# remote_v0_14_fa8ef31d.net
KiCad netlist of a schematic drawn in EAGLE
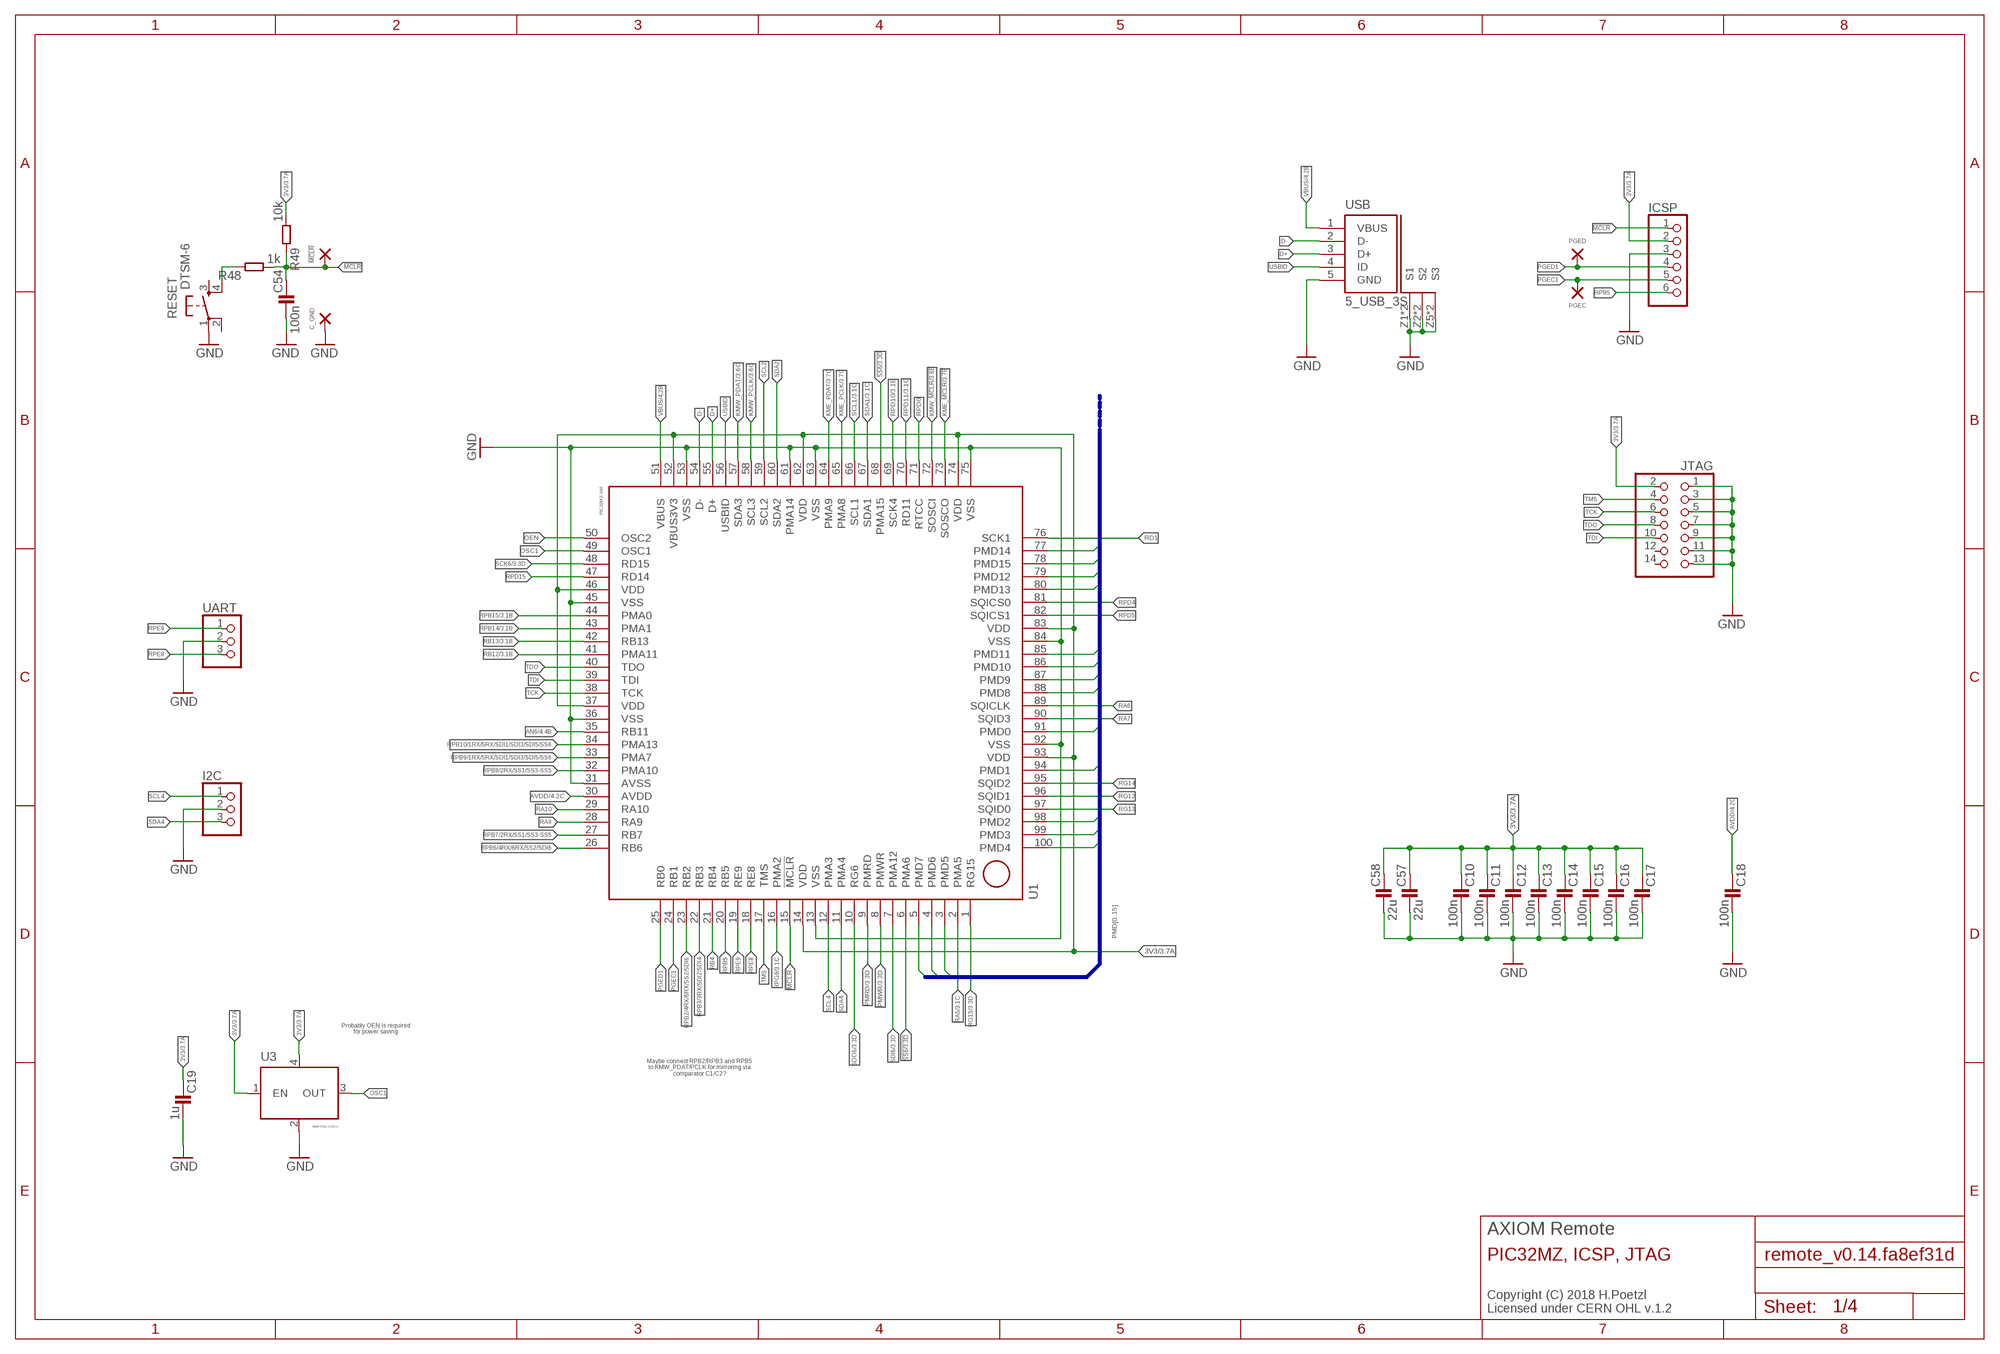
[diagram p0: schematic, sheet 1]
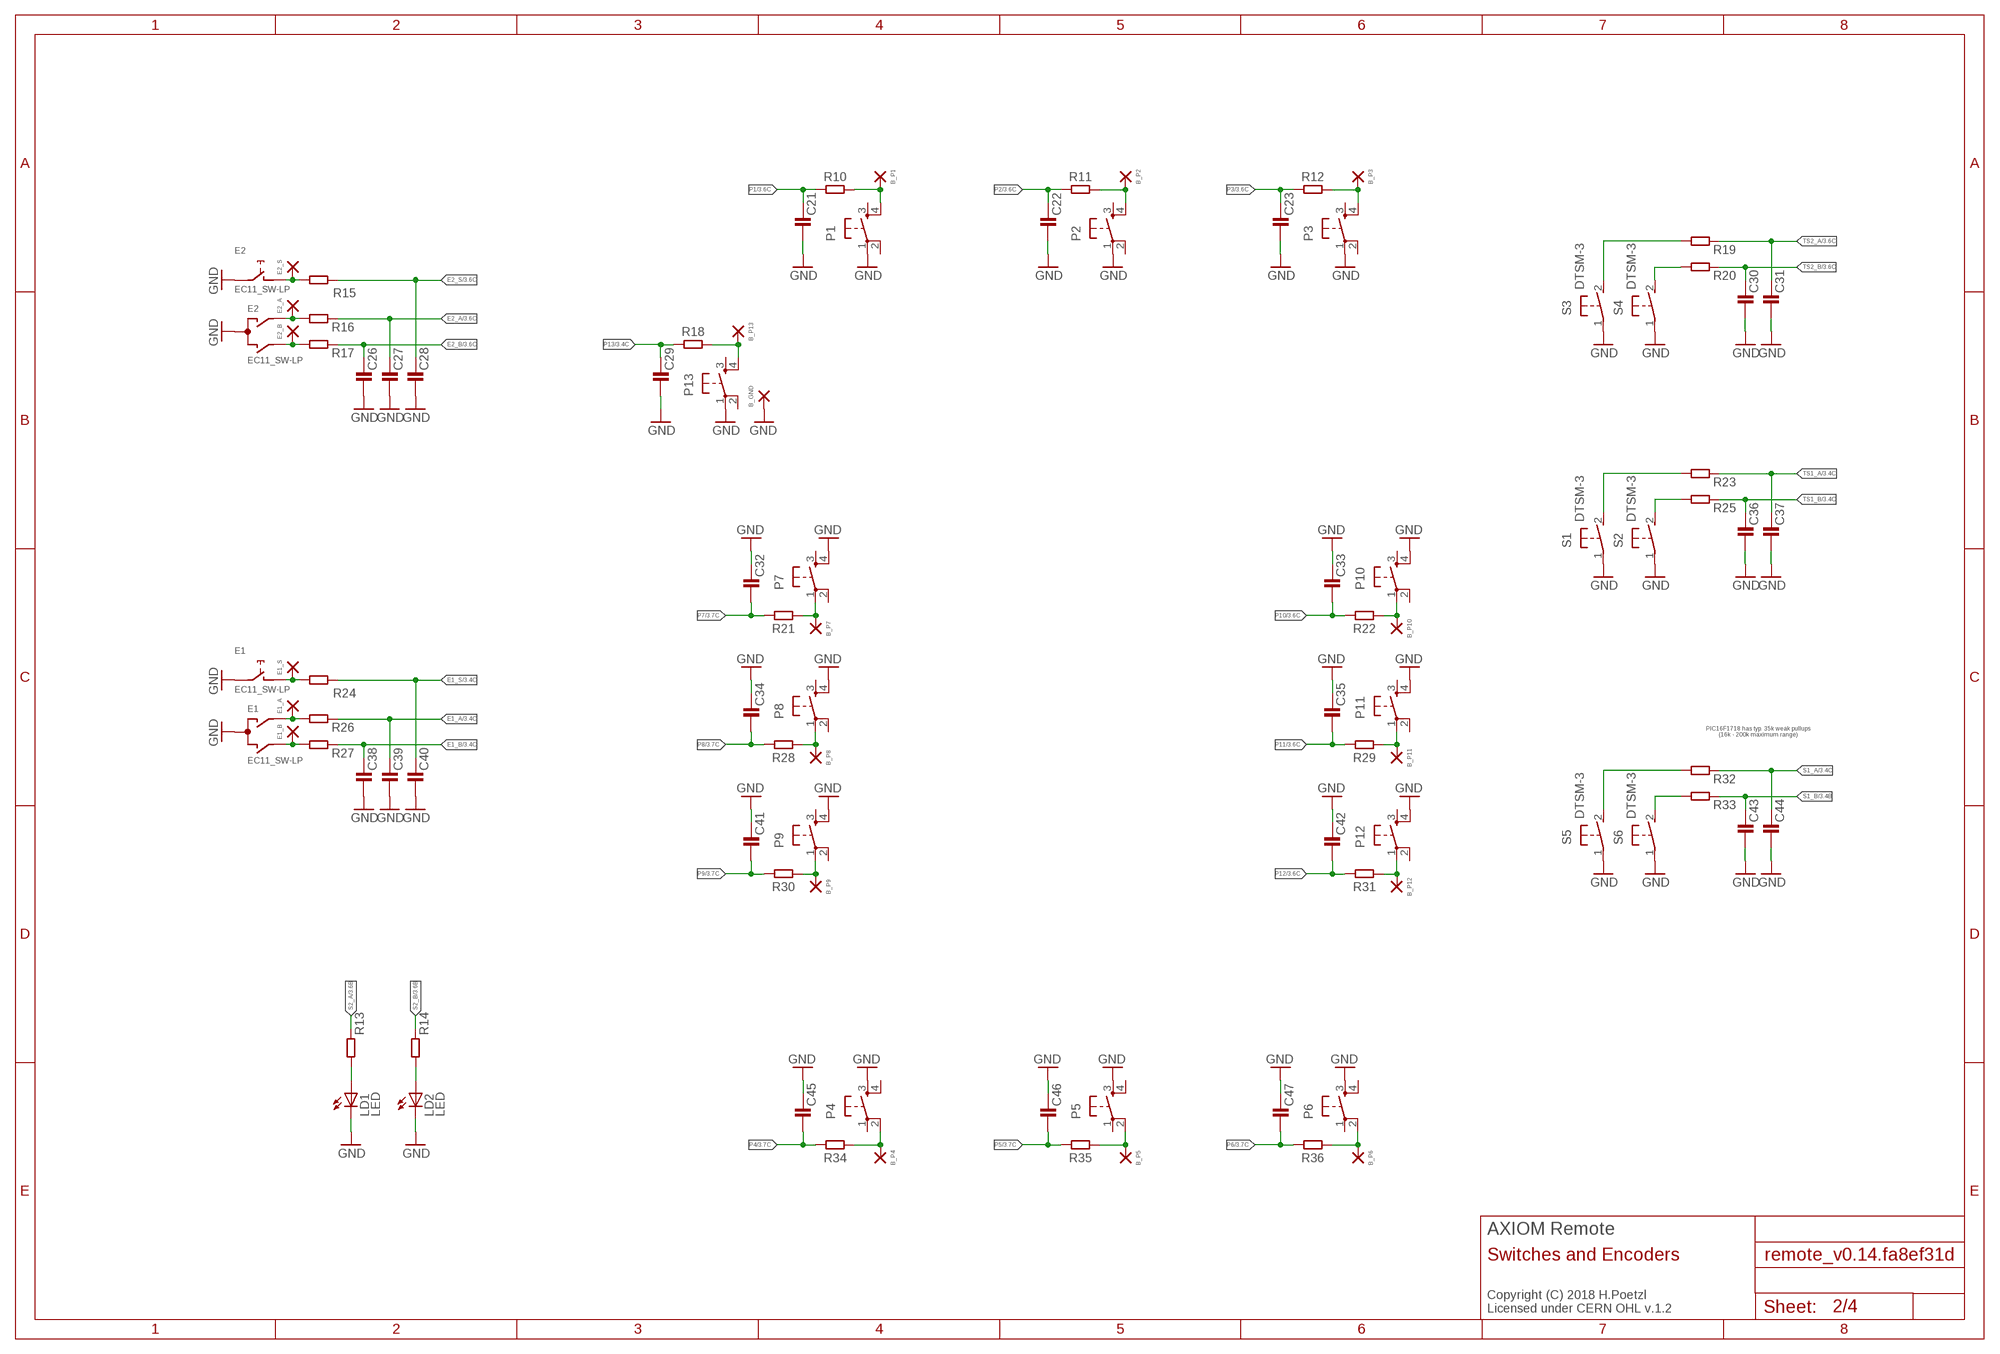
[diagram p1: schematic, sheet 2]
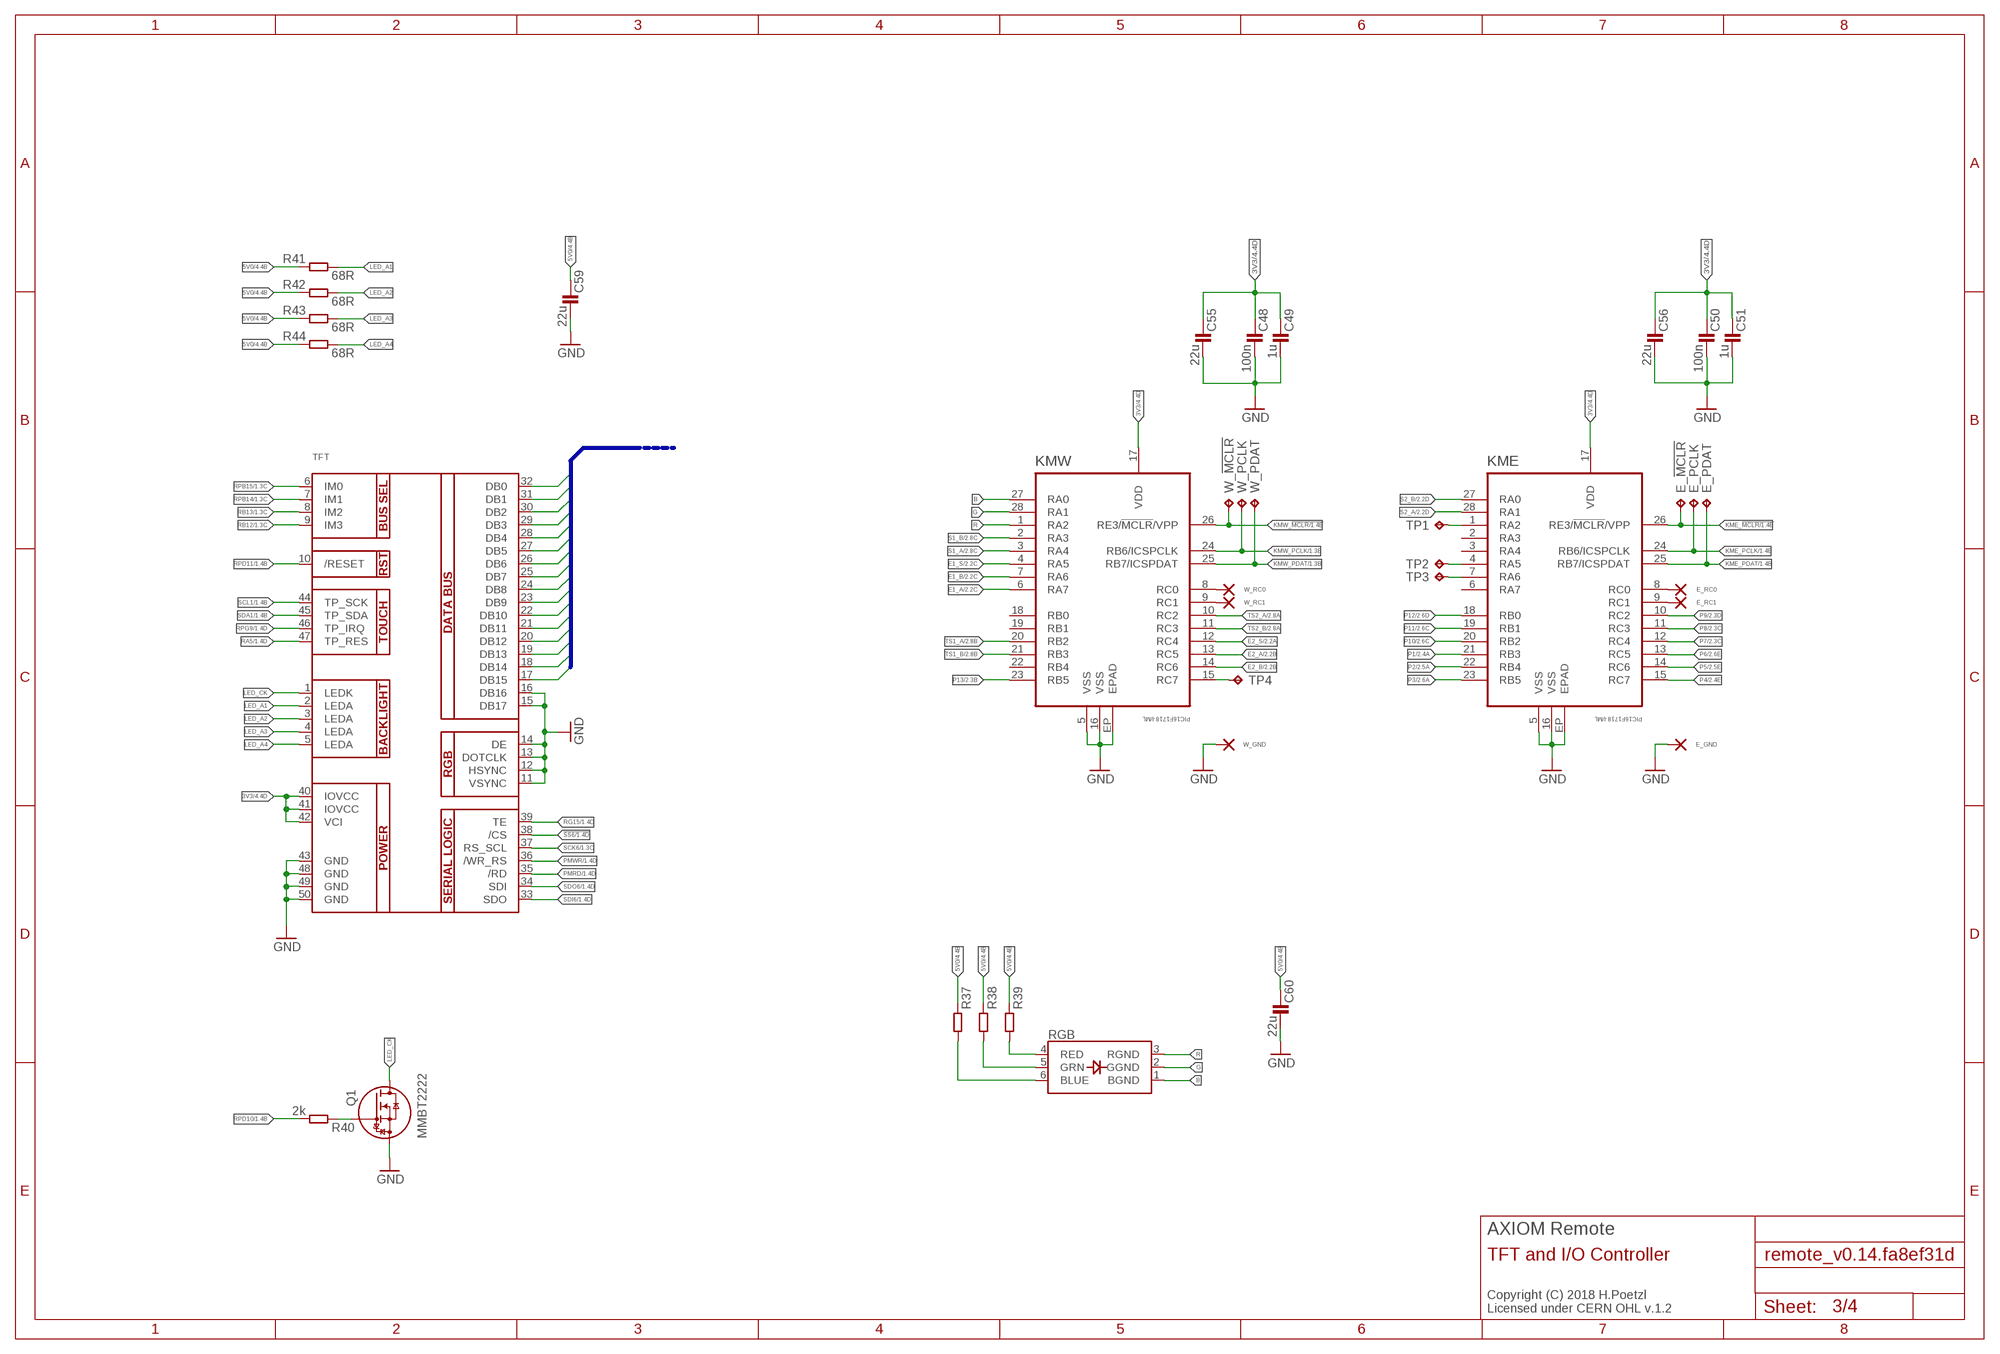
[diagram p2: schematic, sheet 3]
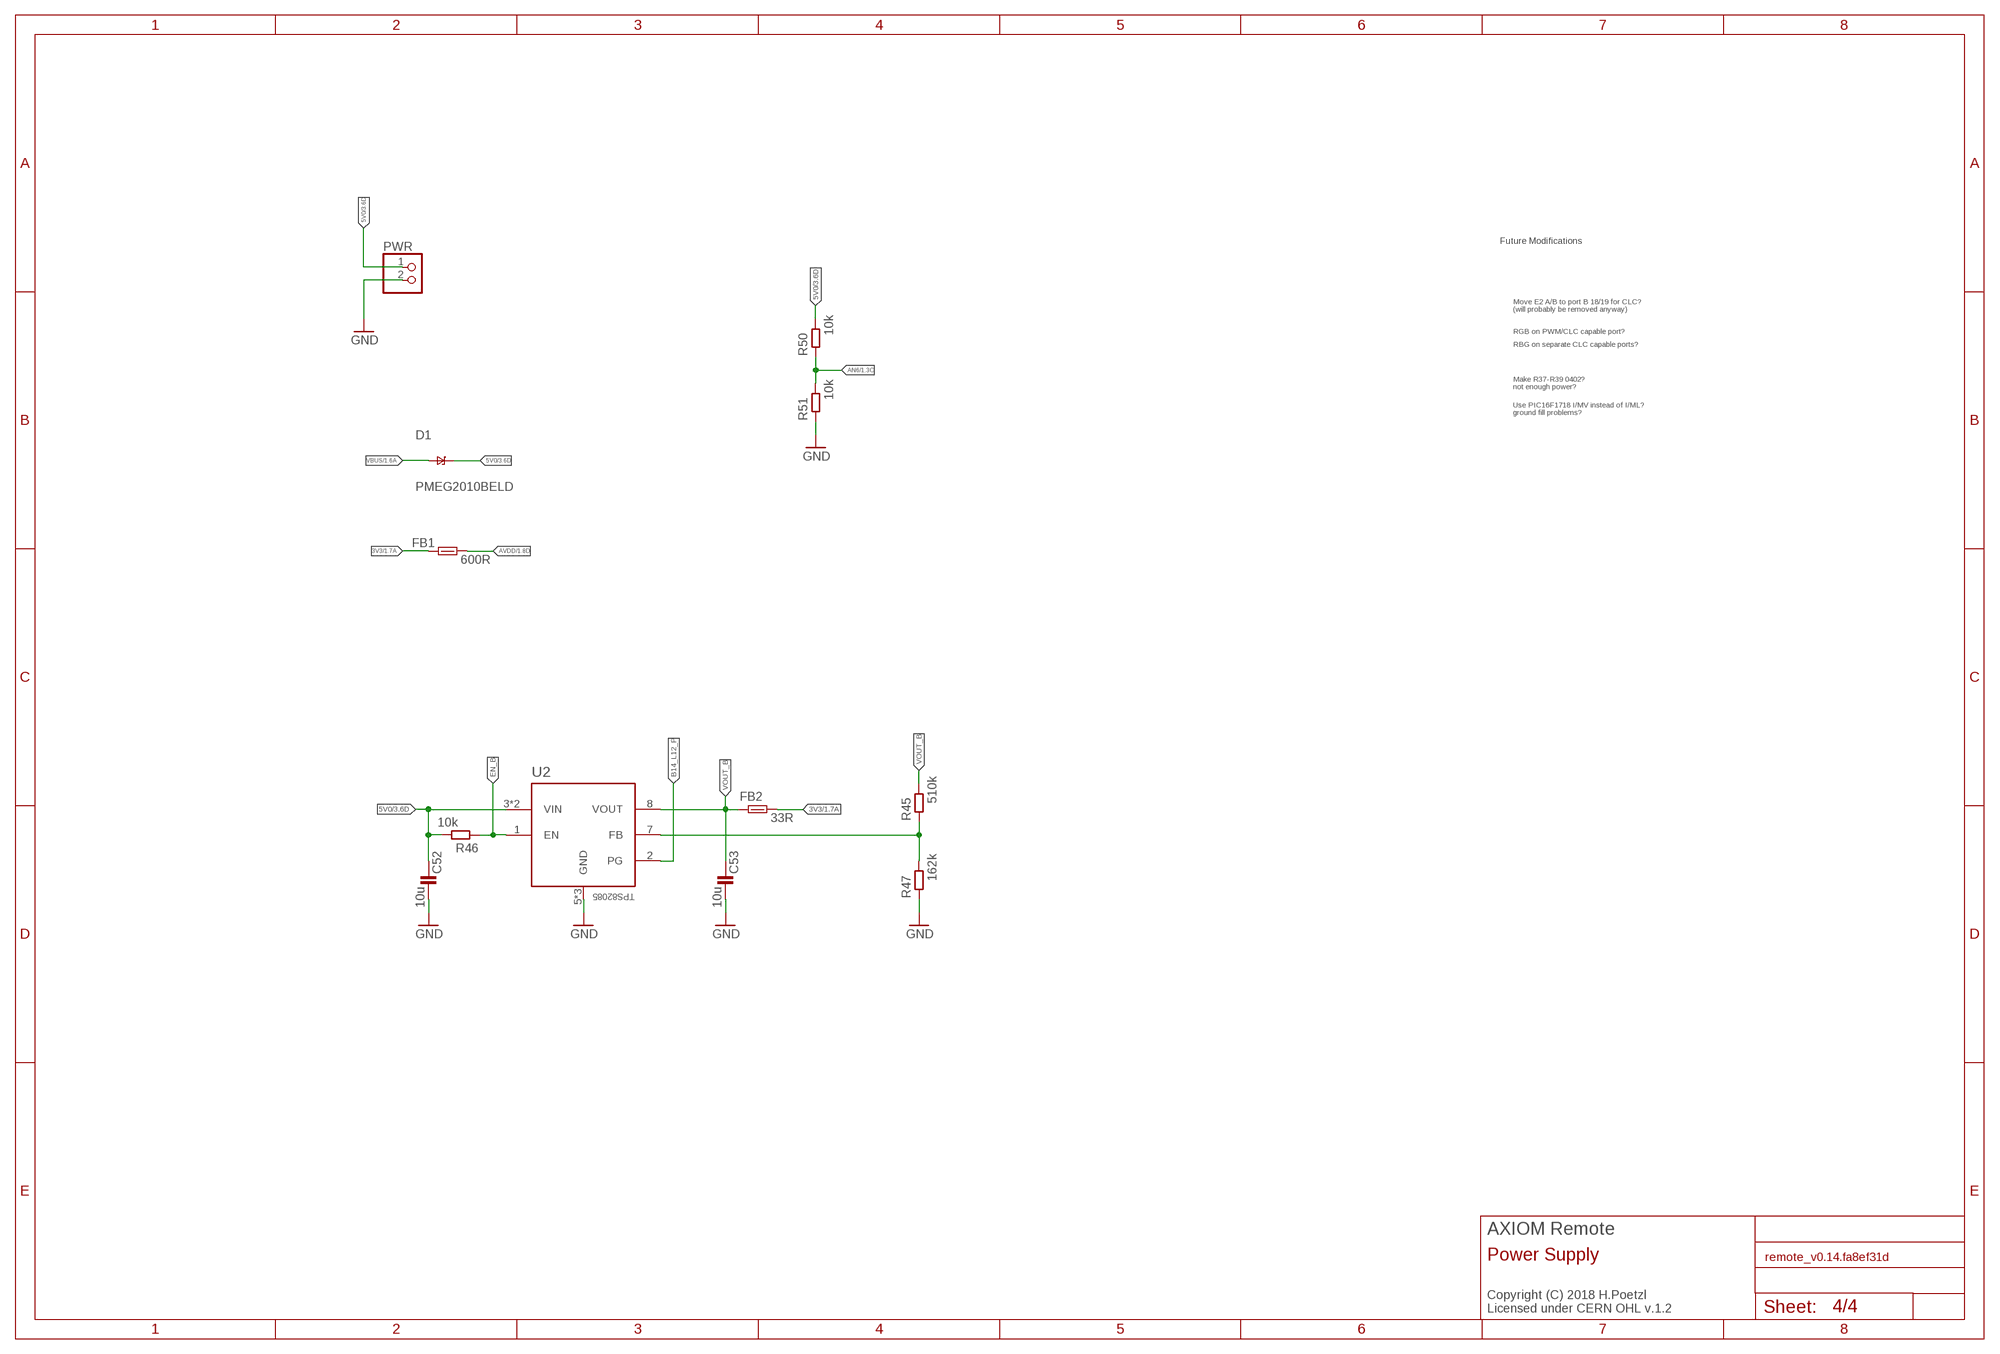
[diagram p3: schematic, sheet 4]

(export (version "E")
  (design (tool "Eeschema 10.0.6"))
  (components
    (comp (ref "B_GND")
      (value "SMD-PAD50X100")
      (footprint "eagle-import:50X100-MIL")
      (libsource (lib "eagle-import") (part "SMD-PAD50X100"))
    )
    (comp (ref "B_P1")
      (value "SMD-PAD50X100")
      (footprint "eagle-import:50X100-MIL")
      (libsource (lib "eagle-import") (part "SMD-PAD50X100"))
    )
    (comp (ref "B_P2")
      (value "SMD-PAD50X100")
      (footprint "eagle-import:50X100-MIL")
      (libsource (lib "eagle-import") (part "SMD-PAD50X100"))
    )
    (comp (ref "B_P3")
      (value "SMD-PAD50X100")
      (footprint "eagle-import:50X100-MIL")
      (libsource (lib "eagle-import") (part "SMD-PAD50X100"))
    )
    (comp (ref "B_P4")
      (value "SMD-PAD50X100")
      (footprint "eagle-import:50X100-MIL")
      (libsource (lib "eagle-import") (part "SMD-PAD50X100"))
    )
    (comp (ref "B_P5")
      (value "SMD-PAD50X100")
      (footprint "eagle-import:50X100-MIL")
      (libsource (lib "eagle-import") (part "SMD-PAD50X100"))
    )
    (comp (ref "B_P6")
      (value "SMD-PAD50X100")
      (footprint "eagle-import:50X100-MIL")
      (libsource (lib "eagle-import") (part "SMD-PAD50X100"))
    )
    (comp (ref "B_P7")
      (value "SMD-PAD50X100")
      (footprint "eagle-import:50X100-MIL")
      (libsource (lib "eagle-import") (part "SMD-PAD50X100"))
    )
    (comp (ref "B_P8")
      (value "SMD-PAD50X100")
      (footprint "eagle-import:50X100-MIL")
      (libsource (lib "eagle-import") (part "SMD-PAD50X100"))
    )
    (comp (ref "B_P9")
      (value "SMD-PAD50X100")
      (footprint "eagle-import:50X100-MIL")
      (libsource (lib "eagle-import") (part "SMD-PAD50X100"))
    )
    (comp (ref "B_P10")
      (value "SMD-PAD50X100")
      (footprint "eagle-import:50X100-MIL")
      (libsource (lib "eagle-import") (part "SMD-PAD50X100"))
    )
    (comp (ref "B_P11")
      (value "SMD-PAD50X100")
      (footprint "eagle-import:50X100-MIL")
      (libsource (lib "eagle-import") (part "SMD-PAD50X100"))
    )
    (comp (ref "B_P12")
      (value "SMD-PAD50X100")
      (footprint "eagle-import:50X100-MIL")
      (libsource (lib "eagle-import") (part "SMD-PAD50X100"))
    )
    (comp (ref "B_P13")
      (value "SMD-PAD50X100")
      (footprint "eagle-import:50X100-MIL")
      (libsource (lib "eagle-import") (part "SMD-PAD50X100"))
    )
    (comp (ref "C21")
      (value "C0402-C")
      (footprint "eagle-import:0402-C")
      (libsource (lib "eagle-import") (part "C0402-C"))
    )
    (comp (ref "C22")
      (value "C0402-C")
      (footprint "eagle-import:0402-C")
      (libsource (lib "eagle-import") (part "C0402-C"))
    )
    (comp (ref "C23")
      (value "C0402-C")
      (footprint "eagle-import:0402-C")
      (libsource (lib "eagle-import") (part "C0402-C"))
    )
    (comp (ref "C26")
      (value "C0402-C")
      (footprint "eagle-import:0402-C")
      (libsource (lib "eagle-import") (part "C0402-C"))
    )
    (comp (ref "C27")
      (value "C0402-C")
      (footprint "eagle-import:0402-C")
      (libsource (lib "eagle-import") (part "C0402-C"))
    )
    (comp (ref "C28")
      (value "C0402-C")
      (footprint "eagle-import:0402-C")
      (libsource (lib "eagle-import") (part "C0402-C"))
    )
    (comp (ref "C29")
      (value "C0402-C")
      (footprint "eagle-import:0402-C")
      (libsource (lib "eagle-import") (part "C0402-C"))
    )
    (comp (ref "C30")
      (value "C0402-C")
      (footprint "eagle-import:0402-C")
      (libsource (lib "eagle-import") (part "C0402-C"))
    )
    (comp (ref "C31")
      (value "C0402-C")
      (footprint "eagle-import:0402-C")
      (libsource (lib "eagle-import") (part "C0402-C"))
    )
    (comp (ref "C32")
      (value "C0402-C")
      (footprint "eagle-import:0402-C")
      (libsource (lib "eagle-import") (part "C0402-C"))
    )
    (comp (ref "C33")
      (value "C0402-C")
      (footprint "eagle-import:0402-C")
      (libsource (lib "eagle-import") (part "C0402-C"))
    )
    (comp (ref "C34")
      (value "C0402-C")
      (footprint "eagle-import:0402-C")
      (libsource (lib "eagle-import") (part "C0402-C"))
    )
    (comp (ref "C35")
      (value "C0402-C")
      (footprint "eagle-import:0402-C")
      (libsource (lib "eagle-import") (part "C0402-C"))
    )
    (comp (ref "C36")
      (value "C0402-C")
      (footprint "eagle-import:0402-C")
      (libsource (lib "eagle-import") (part "C0402-C"))
    )
    (comp (ref "C37")
      (value "C0402-C")
      (footprint "eagle-import:0402-C")
      (libsource (lib "eagle-import") (part "C0402-C"))
    )
    (comp (ref "C38")
      (value "C0402-C")
      (footprint "eagle-import:0402-C")
      (libsource (lib "eagle-import") (part "C0402-C"))
    )
    (comp (ref "C39")
      (value "C0402-C")
      (footprint "eagle-import:0402-C")
      (libsource (lib "eagle-import") (part "C0402-C"))
    )
    (comp (ref "C40")
      (value "C0402-C")
      (footprint "eagle-import:0402-C")
      (libsource (lib "eagle-import") (part "C0402-C"))
    )
    (comp (ref "C41")
      (value "C0402-C")
      (footprint "eagle-import:0402-C")
      (libsource (lib "eagle-import") (part "C0402-C"))
    )
    (comp (ref "C42")
      (value "C0402-C")
      (footprint "eagle-import:0402-C")
      (libsource (lib "eagle-import") (part "C0402-C"))
    )
    (comp (ref "C43")
      (value "C0402-C")
      (footprint "eagle-import:0402-C")
      (libsource (lib "eagle-import") (part "C0402-C"))
    )
    (comp (ref "C44")
      (value "C0402-C")
      (footprint "eagle-import:0402-C")
      (libsource (lib "eagle-import") (part "C0402-C"))
    )
    (comp (ref "C45")
      (value "C0402-C")
      (footprint "eagle-import:0402-C")
      (libsource (lib "eagle-import") (part "C0402-C"))
    )
    (comp (ref "C46")
      (value "C0402-C")
      (footprint "eagle-import:0402-C")
      (libsource (lib "eagle-import") (part "C0402-C"))
    )
    (comp (ref "C47")
      (value "C0402-C")
      (footprint "eagle-import:0402-C")
      (libsource (lib "eagle-import") (part "C0402-C"))
    )
    (comp (ref "E1")
      (value "EC11_SW-LP")
      (footprint "eagle-import:EC11_SW-LP")
      (libsource (lib "eagle-import") (part "EC11_SW-LP"))
    )
    (comp (ref "E1_A")
      (value "SMD-PAD50X100")
      (footprint "eagle-import:50X100-MIL")
      (libsource (lib "eagle-import") (part "SMD-PAD50X100"))
    )
    (comp (ref "E1_B")
      (value "SMD-PAD50X100")
      (footprint "eagle-import:50X100-MIL")
      (libsource (lib "eagle-import") (part "SMD-PAD50X100"))
    )
    (comp (ref "E1_S")
      (value "SMD-PAD50X100")
      (footprint "eagle-import:50X100-MIL")
      (libsource (lib "eagle-import") (part "SMD-PAD50X100"))
    )
    (comp (ref "E2")
      (value "EC11_SW-LP")
      (footprint "eagle-import:EC11_SW-LP")
      (libsource (lib "eagle-import") (part "EC11_SW-LP"))
    )
    (comp (ref "E2_A")
      (value "SMD-PAD50X100")
      (footprint "eagle-import:50X100-MIL")
      (libsource (lib "eagle-import") (part "SMD-PAD50X100"))
    )
    (comp (ref "E2_B")
      (value "SMD-PAD50X100")
      (footprint "eagle-import:50X100-MIL")
      (libsource (lib "eagle-import") (part "SMD-PAD50X100"))
    )
    (comp (ref "E2_S")
      (value "SMD-PAD50X100")
      (footprint "eagle-import:50X100-MIL")
      (libsource (lib "eagle-import") (part "SMD-PAD50X100"))
    )
    (comp (ref "LD1")
      (value "LED")
      (footprint "eagle-import:CHIPLED_0603")
      (libsource (lib "eagle-import") (part "LED"))
    )
    (comp (ref "LD2")
      (value "LED")
      (footprint "eagle-import:CHIPLED_0603")
      (libsource (lib "eagle-import") (part "LED"))
    )
    (comp (ref "P1")
      (value "DTSM-6THT")
      (footprint "eagle-import:6X6-THT")
      (libsource (lib "eagle-import") (part "DTSM-6THT"))
    )
    (comp (ref "P2")
      (value "DTSM-6THT")
      (footprint "eagle-import:6X6-THT")
      (libsource (lib "eagle-import") (part "DTSM-6THT"))
    )
    (comp (ref "P3")
      (value "DTSM-6THT")
      (footprint "eagle-import:6X6-THT")
      (libsource (lib "eagle-import") (part "DTSM-6THT"))
    )
    (comp (ref "P4")
      (value "DTSM-6THT")
      (footprint "eagle-import:6X6-THT")
      (libsource (lib "eagle-import") (part "DTSM-6THT"))
    )
    (comp (ref "P5")
      (value "DTSM-6THT")
      (footprint "eagle-import:6X6-THT")
      (libsource (lib "eagle-import") (part "DTSM-6THT"))
    )
    (comp (ref "P6")
      (value "DTSM-6THT")
      (footprint "eagle-import:6X6-THT")
      (libsource (lib "eagle-import") (part "DTSM-6THT"))
    )
    (comp (ref "P7")
      (value "DTSM-6THT")
      (footprint "eagle-import:6X6-THT")
      (libsource (lib "eagle-import") (part "DTSM-6THT"))
    )
    (comp (ref "P8")
      (value "DTSM-6THT")
      (footprint "eagle-import:6X6-THT")
      (libsource (lib "eagle-import") (part "DTSM-6THT"))
    )
    (comp (ref "P9")
      (value "DTSM-6THT")
      (footprint "eagle-import:6X6-THT")
      (libsource (lib "eagle-import") (part "DTSM-6THT"))
    )
    (comp (ref "P10")
      (value "DTSM-6THT")
      (footprint "eagle-import:6X6-THT")
      (libsource (lib "eagle-import") (part "DTSM-6THT"))
    )
    (comp (ref "P11")
      (value "DTSM-6THT")
      (footprint "eagle-import:6X6-THT")
      (libsource (lib "eagle-import") (part "DTSM-6THT"))
    )
    (comp (ref "P12")
      (value "DTSM-6THT")
      (footprint "eagle-import:6X6-THT")
      (libsource (lib "eagle-import") (part "DTSM-6THT"))
    )
    (comp (ref "P13")
      (value "DTSM-6THT")
      (footprint "eagle-import:6X6-THT")
      (libsource (lib "eagle-import") (part "DTSM-6THT"))
    )
    (comp (ref "R10")
      (value "R0402-C")
      (footprint "eagle-import:0402-C")
      (libsource (lib "eagle-import") (part "R0402-C"))
    )
    (comp (ref "R11")
      (value "R0402-C")
      (footprint "eagle-import:0402-C")
      (libsource (lib "eagle-import") (part "R0402-C"))
    )
    (comp (ref "R12")
      (value "R0402-C")
      (footprint "eagle-import:0402-C")
      (libsource (lib "eagle-import") (part "R0402-C"))
    )
    (comp (ref "R13")
      (value "R0402-C")
      (footprint "eagle-import:0402-C")
      (libsource (lib "eagle-import") (part "R0402-C"))
    )
    (comp (ref "R14")
      (value "R0402-C")
      (footprint "eagle-import:0402-C")
      (libsource (lib "eagle-import") (part "R0402-C"))
    )
    (comp (ref "R15")
      (value "R0402-C")
      (footprint "eagle-import:0402-C")
      (libsource (lib "eagle-import") (part "R0402-C"))
    )
    (comp (ref "R16")
      (value "R0402-C")
      (footprint "eagle-import:0402-C")
      (libsource (lib "eagle-import") (part "R0402-C"))
    )
    (comp (ref "R17")
      (value "R0402-C")
      (footprint "eagle-import:0402-C")
      (libsource (lib "eagle-import") (part "R0402-C"))
    )
    (comp (ref "R18")
      (value "R0402-C")
      (footprint "eagle-import:0402-C")
      (libsource (lib "eagle-import") (part "R0402-C"))
    )
    (comp (ref "R19")
      (value "R0402-C")
      (footprint "eagle-import:0402-C")
      (libsource (lib "eagle-import") (part "R0402-C"))
    )
    (comp (ref "R20")
      (value "R0402-C")
      (footprint "eagle-import:0402-C")
      (libsource (lib "eagle-import") (part "R0402-C"))
    )
    (comp (ref "R21")
      (value "R0402-C")
      (footprint "eagle-import:0402-C")
      (libsource (lib "eagle-import") (part "R0402-C"))
    )
    (comp (ref "R22")
      (value "R0402-C")
      (footprint "eagle-import:0402-C")
      (libsource (lib "eagle-import") (part "R0402-C"))
    )
    (comp (ref "R23")
      (value "R0402-C")
      (footprint "eagle-import:0402-C")
      (libsource (lib "eagle-import") (part "R0402-C"))
    )
    (comp (ref "R24")
      (value "R0402-C")
      (footprint "eagle-import:0402-C")
      (libsource (lib "eagle-import") (part "R0402-C"))
    )
    (comp (ref "R25")
      (value "R0402-C")
      (footprint "eagle-import:0402-C")
      (libsource (lib "eagle-import") (part "R0402-C"))
    )
    (comp (ref "R26")
      (value "R0402-C")
      (footprint "eagle-import:0402-C")
      (libsource (lib "eagle-import") (part "R0402-C"))
    )
    (comp (ref "R27")
      (value "R0402-C")
      (footprint "eagle-import:0402-C")
      (libsource (lib "eagle-import") (part "R0402-C"))
    )
    (comp (ref "R28")
      (value "R0402-C")
      (footprint "eagle-import:0402-C")
      (libsource (lib "eagle-import") (part "R0402-C"))
    )
    (comp (ref "R29")
      (value "R0402-C")
      (footprint "eagle-import:0402-C")
      (libsource (lib "eagle-import") (part "R0402-C"))
    )
    (comp (ref "R30")
      (value "R0402-C")
      (footprint "eagle-import:0402-C")
      (libsource (lib "eagle-import") (part "R0402-C"))
    )
    (comp (ref "R31")
      (value "R0402-C")
      (footprint "eagle-import:0402-C")
      (libsource (lib "eagle-import") (part "R0402-C"))
    )
    (comp (ref "R32")
      (value "R0402-C")
      (footprint "eagle-import:0402-C")
      (libsource (lib "eagle-import") (part "R0402-C"))
    )
    (comp (ref "R33")
      (value "R0402-C")
      (footprint "eagle-import:0402-C")
      (libsource (lib "eagle-import") (part "R0402-C"))
    )
    (comp (ref "R34")
      (value "R0402-C")
      (footprint "eagle-import:0402-C")
      (libsource (lib "eagle-import") (part "R0402-C"))
    )
    (comp (ref "R35")
      (value "R0402-C")
      (footprint "eagle-import:0402-C")
      (libsource (lib "eagle-import") (part "R0402-C"))
    )
    (comp (ref "R36")
      (value "R0402-C")
      (footprint "eagle-import:0402-C")
      (libsource (lib "eagle-import") (part "R0402-C"))
    )
    (comp (ref "S1")
      (value "DTSM-3")
      (footprint "eagle-import:DTSM-3")
      (libsource (lib "eagle-import") (part "DTSM-3"))
    )
    (comp (ref "S2")
      (value "DTSM-3")
      (footprint "eagle-import:DTSM-3")
      (libsource (lib "eagle-import") (part "DTSM-3"))
    )
    (comp (ref "S3")
      (value "DTSM-3")
      (footprint "eagle-import:DTSM-3")
      (libsource (lib "eagle-import") (part "DTSM-3"))
    )
    (comp (ref "S4")
      (value "DTSM-3")
      (footprint "eagle-import:DTSM-3")
      (libsource (lib "eagle-import") (part "DTSM-3"))
    )
    (comp (ref "S5")
      (value "DTSM-3")
      (footprint "eagle-import:DTSM-3")
      (libsource (lib "eagle-import") (part "DTSM-3"))
    )
    (comp (ref "S6")
      (value "DTSM-3")
      (footprint "eagle-import:DTSM-3")
      (libsource (lib "eagle-import") (part "DTSM-3"))
    )
    (comp (ref "!MCLR")
      (value "SMD-PAD50X100")
      (footprint "eagle-import:50X100-MIL")
      (libsource (lib "eagle-import") (part "SMD-PAD50X100"))
    )
    (comp (ref "C10")
      (value "100n")
      (footprint "eagle-import:0402-C")
      (libsource (lib "eagle-import") (part "C0402-C"))
    )
    (comp (ref "C11")
      (value "100n")
      (footprint "eagle-import:0402-C")
      (libsource (lib "eagle-import") (part "C0402-C"))
    )
    (comp (ref "C12")
      (value "100n")
      (footprint "eagle-import:0402-C")
      (libsource (lib "eagle-import") (part "C0402-C"))
    )
    (comp (ref "C13")
      (value "100n")
      (footprint "eagle-import:0402-C")
      (libsource (lib "eagle-import") (part "C0402-C"))
    )
    (comp (ref "C14")
      (value "100n")
      (footprint "eagle-import:0402-C")
      (libsource (lib "eagle-import") (part "C0402-C"))
    )
    (comp (ref "C15")
      (value "100n")
      (footprint "eagle-import:0402-C")
      (libsource (lib "eagle-import") (part "C0402-C"))
    )
    (comp (ref "C16")
      (value "100n")
      (footprint "eagle-import:0402-C")
      (libsource (lib "eagle-import") (part "C0402-C"))
    )
    (comp (ref "C17")
      (value "100n")
      (footprint "eagle-import:0402-C")
      (libsource (lib "eagle-import") (part "C0402-C"))
    )
    (comp (ref "C18")
      (value "100n")
      (footprint "eagle-import:0402-C")
      (libsource (lib "eagle-import") (part "C0402-C"))
    )
    (comp (ref "C19")
      (value "1u")
      (footprint "eagle-import:0402-C")
      (libsource (lib "eagle-import") (part "C0402-C"))
    )
    (comp (ref "C54")
      (value "100n")
      (footprint "eagle-import:0402-C")
      (libsource (lib "eagle-import") (part "C0402-C"))
    )
    (comp (ref "C57")
      (value "22u")
      (footprint "eagle-import:0805-C")
      (libsource (lib "eagle-import") (part "C0805-C"))
    )
    (comp (ref "C58")
      (value "22u")
      (footprint "eagle-import:0805-C")
      (libsource (lib "eagle-import") (part "C0805-C"))
    )
    (comp (ref "C_GND")
      (value "SMD-PAD50X100")
      (footprint "eagle-import:50X100-MIL")
      (libsource (lib "eagle-import") (part "SMD-PAD50X100"))
    )
    (comp (ref "I2C")
      (value "PINHD-1X03_2.54-90°")
      (footprint "eagle-import:1X03_90")
      (libsource (lib "eagle-import") (part "PINHD-1X03_2.54-90°"))
    )
    (comp (ref "ICSP")
      (value "PINHD-1X6/90")
      (footprint "eagle-import:1X06_90")
      (libsource (lib "eagle-import") (part "PINHD-1X6/90"))
    )
    (comp (ref "JTAG")
      (value "PINHD-2X07_2.00")
      (footprint "eagle-import:2X07M")
      (libsource (lib "eagle-import") (part "PINHD-2X07_2.00"))
    )
    (comp (ref "PGEC")
      (value "SMD-PAD50X100")
      (footprint "eagle-import:50X100-MIL")
      (libsource (lib "eagle-import") (part "SMD-PAD50X100"))
    )
    (comp (ref "PGED")
      (value "SMD-PAD50X100")
      (footprint "eagle-import:50X100-MIL")
      (libsource (lib "eagle-import") (part "SMD-PAD50X100"))
    )
    (comp (ref "R48")
      (value "1k")
      (footprint "eagle-import:0402-C")
      (libsource (lib "eagle-import") (part "R0402-C"))
    )
    (comp (ref "R49")
      (value "10k")
      (footprint "eagle-import:0402-C")
      (libsource (lib "eagle-import") (part "R0402-C"))
    )
    (comp (ref "RESET")
      (value "DTSM-6")
      (footprint "eagle-import:3X4MM")
      (libsource (lib "eagle-import") (part "DTSM-6"))
    )
    (comp (ref "U1")
      (value "PIC32MZ-100")
      (footprint "eagle-import:QFP40P1200X1200X120-100N")
      (libsource (lib "eagle-import") (part "PIC32MZ-100"))
    )
    (comp (ref "U3")
      (value "SMD-OSC-2.0X1.6")
      (footprint "eagle-import:2.0X1.6")
      (libsource (lib "eagle-import") (part "SMD-OSC-2.0X1.6"))
    )
    (comp (ref "UART")
      (value "PINHD-1X03_2.54-90°")
      (footprint "eagle-import:1X03_90")
      (libsource (lib "eagle-import") (part "PINHD-1X03_2.54-90°"))
    )
    (comp (ref "USB")
      (value "5_USB_3S")
      (footprint "eagle-import:MICRO-AB-H-SMT")
      (libsource (lib "eagle-import") (part "5_USB_3S"))
    )
    (comp (ref "C48")
      (value "100n")
      (footprint "eagle-import:0402-C")
      (libsource (lib "eagle-import") (part "C0402-C"))
    )
    (comp (ref "C49")
      (value "1u")
      (footprint "eagle-import:0402-C")
      (libsource (lib "eagle-import") (part "C0402-C"))
    )
    (comp (ref "C50")
      (value "100n")
      (footprint "eagle-import:0402-C")
      (libsource (lib "eagle-import") (part "C0402-C"))
    )
    (comp (ref "C51")
      (value "1u")
      (footprint "eagle-import:0402-C")
      (libsource (lib "eagle-import") (part "C0402-C"))
    )
    (comp (ref "C55")
      (value "22u")
      (footprint "eagle-import:0805-C")
      (libsource (lib "eagle-import") (part "C0805-C"))
    )
    (comp (ref "C56")
      (value "22u")
      (footprint "eagle-import:0805-C")
      (libsource (lib "eagle-import") (part "C0805-C"))
    )
    (comp (ref "C59")
      (value "22u")
      (footprint "eagle-import:0805-C")
      (libsource (lib "eagle-import") (part "C0805-C"))
    )
    (comp (ref "C60")
      (value "22u")
      (footprint "eagle-import:0805-C")
      (libsource (lib "eagle-import") (part "C0805-C"))
    )
    (comp (ref "E_!MCLR")
      (value "TPTP12R")
      (footprint "eagle-import:TP12R")
      (libsource (lib "eagle-import") (part "TPTP12R"))
    )
    (comp (ref "E_GND")
      (value "SMD-PAD50X100")
      (footprint "eagle-import:50X100-MIL")
      (libsource (lib "eagle-import") (part "SMD-PAD50X100"))
    )
    (comp (ref "E_PCLK")
      (value "TPTP12R")
      (footprint "eagle-import:TP12R")
      (libsource (lib "eagle-import") (part "TPTP12R"))
    )
    (comp (ref "E_PDAT")
      (value "TPTP12R")
      (footprint "eagle-import:TP12R")
      (libsource (lib "eagle-import") (part "TPTP12R"))
    )
    (comp (ref "E_RC0")
      (value "SMD-PAD50X100")
      (footprint "eagle-import:50X100-MIL")
      (libsource (lib "eagle-import") (part "SMD-PAD50X100"))
    )
    (comp (ref "E_RC1")
      (value "SMD-PAD50X100")
      (footprint "eagle-import:50X100-MIL")
      (libsource (lib "eagle-import") (part "SMD-PAD50X100"))
    )
    (comp (ref "KME")
      (value "PIC16F1718-I/ML")
      (footprint "eagle-import:QFN65P600X600X100-29N")
      (libsource (lib "eagle-import") (part "PIC16F1718-I/ML"))
    )
    (comp (ref "KMW")
      (value "PIC16F1718-I/ML")
      (footprint "eagle-import:QFN65P600X600X100-29N")
      (libsource (lib "eagle-import") (part "PIC16F1718-I/ML"))
    )
    (comp (ref "Q1")
      (value "MMBT2222")
      (footprint "eagle-import:SOT323")
      (libsource (lib "eagle-import") (part "NX3008NBKW"))
    )
    (comp (ref "R37")
      (value "R0603-C")
      (footprint "eagle-import:0603-C")
      (libsource (lib "eagle-import") (part "R0603-C"))
    )
    (comp (ref "R38")
      (value "R0603-C")
      (footprint "eagle-import:0603-C")
      (libsource (lib "eagle-import") (part "R0603-C"))
    )
    (comp (ref "R39")
      (value "R0603-C")
      (footprint "eagle-import:0603-C")
      (libsource (lib "eagle-import") (part "R0603-C"))
    )
    (comp (ref "R40")
      (value "2k")
      (footprint "eagle-import:0402-C")
      (libsource (lib "eagle-import") (part "R0402-C"))
    )
    (comp (ref "R41")
      (value "68R")
      (footprint "eagle-import:0805-C")
      (libsource (lib "eagle-import") (part "R0805-C"))
    )
    (comp (ref "R42")
      (value "68R")
      (footprint "eagle-import:0805-C")
      (libsource (lib "eagle-import") (part "R0805-C"))
    )
    (comp (ref "R43")
      (value "68R")
      (footprint "eagle-import:0805-C")
      (libsource (lib "eagle-import") (part "R0805-C"))
    )
    (comp (ref "R44")
      (value "68R")
      (footprint "eagle-import:0805-C")
      (libsource (lib "eagle-import") (part "R0805-C"))
    )
    (comp (ref "RGB")
      (value "LED_RGB_PLCC6CREE-CLV6A")
      (footprint "eagle-import:RGBLED_PLCC6")
      (libsource (lib "eagle-import") (part "LED_RGB_PLCC6CREE-CLV6A"))
    )
    (comp (ref "TFT")
      (value "DISP_LCD_CTP28_SAMPLE")
      (footprint "eagle-import:TFT_2.83IN_240X320_50PIN")
      (libsource (lib "eagle-import") (part "DISP_LCD_CTP28_SAMPLE"))
    )
    (comp (ref "TP1")
      (value "TPTP12R")
      (footprint "eagle-import:TP12R")
      (libsource (lib "eagle-import") (part "TPTP12R"))
    )
    (comp (ref "TP2")
      (value "TPTP12R")
      (footprint "eagle-import:TP12R")
      (libsource (lib "eagle-import") (part "TPTP12R"))
    )
    (comp (ref "TP3")
      (value "TPTP12R")
      (footprint "eagle-import:TP12R")
      (libsource (lib "eagle-import") (part "TPTP12R"))
    )
    (comp (ref "TP4")
      (value "TPTP12R")
      (footprint "eagle-import:TP12R")
      (libsource (lib "eagle-import") (part "TPTP12R"))
    )
    (comp (ref "W_!MCLR")
      (value "TPTP12R")
      (footprint "eagle-import:TP12R")
      (libsource (lib "eagle-import") (part "TPTP12R"))
    )
    (comp (ref "W_GND")
      (value "SMD-PAD50X100")
      (footprint "eagle-import:50X100-MIL")
      (libsource (lib "eagle-import") (part "SMD-PAD50X100"))
    )
    (comp (ref "W_PCLK")
      (value "TPTP12R")
      (footprint "eagle-import:TP12R")
      (libsource (lib "eagle-import") (part "TPTP12R"))
    )
    (comp (ref "W_PDAT")
      (value "TPTP12R")
      (footprint "eagle-import:TP12R")
      (libsource (lib "eagle-import") (part "TPTP12R"))
    )
    (comp (ref "W_RC0")
      (value "SMD-PAD50X100")
      (footprint "eagle-import:50X100-MIL")
      (libsource (lib "eagle-import") (part "SMD-PAD50X100"))
    )
    (comp (ref "W_RC1")
      (value "SMD-PAD50X100")
      (footprint "eagle-import:50X100-MIL")
      (libsource (lib "eagle-import") (part "SMD-PAD50X100"))
    )
    (comp (ref "C52")
      (value "10u")
      (footprint "eagle-import:0603-C")
      (libsource (lib "eagle-import") (part "C0603-C"))
    )
    (comp (ref "C53")
      (value "10u")
      (footprint "eagle-import:0603-C")
      (libsource (lib "eagle-import") (part "C0603-C"))
    )
    (comp (ref "D1")
      (value "PMEG2010BELD")
      (footprint "eagle-import:DFN1006D-2")
      (libsource (lib "eagle-import") (part "PMEG2010BELD"))
    )
    (comp (ref "FB1")
      (value "600R")
      (footprint "eagle-import:0402-C")
      (libsource (lib "eagle-import") (part "FB0402-C"))
    )
    (comp (ref "FB2")
      (value "33R")
      (footprint "eagle-import:0603-C")
      (libsource (lib "eagle-import") (part "FB0603-C"))
    )
    (comp (ref "PWR")
      (value "PINHD-1X02_2.54-90°")
      (footprint "eagle-import:1X02_90")
      (libsource (lib "eagle-import") (part "PINHD-1X02_2.54-90°"))
    )
    (comp (ref "R45")
      (value "510k")
      (footprint "eagle-import:0402-C")
      (libsource (lib "eagle-import") (part "R0402-C"))
    )
    (comp (ref "R46")
      (value "10k")
      (footprint "eagle-import:0402-C")
      (libsource (lib "eagle-import") (part "R0402-C"))
    )
    (comp (ref "R47")
      (value "162k")
      (footprint "eagle-import:0402-C")
      (libsource (lib "eagle-import") (part "R0402-C"))
    )
    (comp (ref "R50")
      (value "10k")
      (footprint "eagle-import:0402-C")
      (libsource (lib "eagle-import") (part "R0402-C"))
    )
    (comp (ref "R51")
      (value "10k")
      (footprint "eagle-import:0402-C")
      (libsource (lib "eagle-import") (part "R0402-C"))
    )
    (comp (ref "U2")
      (value "TPS82085")
      (footprint "eagle-import:MICROSIP")
      (libsource (lib "eagle-import") (part "TPS82085"))
    )
  )
  (nets
    (net (code "2") (name "3V3") (class "Default")
      (node (ref "C10") (pin "1") (pinfunction "1_1") (pintype "passive"))
      (node (ref "C11") (pin "1") (pinfunction "1_1") (pintype "passive"))
      (node (ref "C12") (pin "1") (pinfunction "1_1") (pintype "passive"))
      (node (ref "C13") (pin "1") (pinfunction "1_1") (pintype "passive"))
      (node (ref "C14") (pin "1") (pinfunction "1_1") (pintype "passive"))
      (node (ref "C15") (pin "1") (pinfunction "1_1") (pintype "passive"))
      (node (ref "C16") (pin "1") (pinfunction "1_1") (pintype "passive"))
      (node (ref "C17") (pin "1") (pinfunction "1_1") (pintype "passive"))
      (node (ref "C19") (pin "1") (pinfunction "1_1") (pintype "passive"))
      (node (ref "C48") (pin "1") (pinfunction "1_1") (pintype "passive"))
      (node (ref "C49") (pin "1") (pinfunction "1_1") (pintype "passive"))
      (node (ref "C50") (pin "1") (pinfunction "1_1") (pintype "passive"))
      (node (ref "C51") (pin "1") (pinfunction "1_1") (pintype "passive"))
      (node (ref "C55") (pin "1") (pinfunction "1_1") (pintype "passive"))
      (node (ref "C56") (pin "1") (pinfunction "1_1") (pintype "passive"))
      (node (ref "C57") (pin "1") (pinfunction "1_1") (pintype "passive"))
      (node (ref "C58") (pin "1") (pinfunction "1_1") (pintype "passive"))
      (node (ref "FB1") (pin "1") (pinfunction "1_1") (pintype "passive"))
      (node (ref "FB2") (pin "2") (pinfunction "2_2") (pintype "passive"))
      (node (ref "ICSP") (pin "2") (pinfunction "2_2") (pintype "passive"))
      (node (ref "JTAG") (pin "2") (pinfunction "2_2") (pintype "passive"))
      (node (ref "KME") (pin "17") (pinfunction "VDD_17") (pintype "power_in"))
      (node (ref "KMW") (pin "17") (pinfunction "VDD_17") (pintype "power_in"))
      (node (ref "R49") (pin "2") (pinfunction "2_2") (pintype "passive"))
      (node (ref "TFT") (pin "40") (pinfunction "IOVCC_40") (pintype "bidirectional"))
      (node (ref "TFT") (pin "41") (pinfunction "IOVCC_41") (pintype "bidirectional"))
      (node (ref "TFT") (pin "42") (pinfunction "VCI_42") (pintype "bidirectional"))
      (node (ref "U1") (pin "14") (pinfunction "VDD_14") (pintype "power_in"))
      (node (ref "U1") (pin "37") (pinfunction "VDD_37") (pintype "power_in"))
      (node (ref "U1") (pin "46") (pinfunction "VDD_46") (pintype "power_in"))
      (node (ref "U1") (pin "52") (pinfunction "VBUS3V3_52") (pintype "power_in"))
      (node (ref "U1") (pin "62") (pinfunction "VDD_62") (pintype "power_in"))
      (node (ref "U1") (pin "74") (pinfunction "VDD_74") (pintype "power_in"))
      (node (ref "U1") (pin "83") (pinfunction "VDD_83") (pintype "power_in"))
      (node (ref "U1") (pin "93") (pinfunction "VDD_93") (pintype "power_in"))
      (node (ref "U3") (pin "1") (pinfunction "EN_1") (pintype "input"))
      (node (ref "U3") (pin "4") (pinfunction "VDD_4") (pintype "power_in"))
    )
    (net (code "3") (name "5V0") (class "Default")
      (node (ref "C52") (pin "1") (pinfunction "1_1") (pintype "passive"))
      (node (ref "C59") (pin "1") (pinfunction "1_1") (pintype "passive"))
      (node (ref "C60") (pin "1") (pinfunction "1_1") (pintype "passive"))
      (node (ref "D1") (pin "C") (pinfunction "K_C") (pintype "passive"))
      (node (ref "PWR") (pin "1") (pinfunction "1_1") (pintype "passive"))
      (node (ref "R37") (pin "1") (pinfunction "1_1") (pintype "passive"))
      (node (ref "R38") (pin "1") (pinfunction "1_1") (pintype "passive"))
      (node (ref "R39") (pin "1") (pinfunction "1_1") (pintype "passive"))
      (node (ref "R41") (pin "1") (pinfunction "1_1") (pintype "passive"))
      (node (ref "R42") (pin "1") (pinfunction "1_1") (pintype "passive"))
      (node (ref "R43") (pin "1") (pinfunction "1_1") (pintype "passive"))
      (node (ref "R44") (pin "1") (pinfunction "1_1") (pintype "passive"))
      (node (ref "R46") (pin "2") (pinfunction "2_2") (pintype "passive"))
      (node (ref "R50") (pin "2") (pinfunction "2_2") (pintype "passive"))
      (node (ref "U2") (pin "3") (pinfunction "VIN_3") (pintype "power_in"))
      (node (ref "U2") (pin "4") (pinfunction "VIN_4") (pintype "power_in"))
    )
    (net (code "4") (name "AN6") (class "Default")
      (node (ref "R50") (pin "1") (pinfunction "1_1") (pintype "passive"))
      (node (ref "R51") (pin "2") (pinfunction "2_2") (pintype "passive"))
      (node (ref "U1") (pin "35") (pinfunction "RB11_35") (pintype "bidirectional"))
    )
    (net (code "5") (name "AVDD") (class "Default")
      (node (ref "C18") (pin "1") (pinfunction "1_1") (pintype "passive"))
      (node (ref "FB1") (pin "2") (pinfunction "2_2") (pintype "passive"))
      (node (ref "U1") (pin "30") (pinfunction "AVDD_30") (pintype "power_in"))
    )
    (net (code "6") (name "B") (class "Default")
      (node (ref "KMW") (pin "27") (pinfunction "RA0_27") (pintype "bidirectional"))
      (node (ref "RGB") (pin "1") (pinfunction "BGND_1") (pintype "power_in"))
    )
    (net (code "7") (name "B14_L12_P") (class "Default")
      (node (ref "U2") (pin "2") (pinfunction "PG_2") (pintype "power_in"))
    )
    (net (code "8") (name "D+") (class "Default")
      (node (ref "U1") (pin "55") (pinfunction "D+_55") (pintype "bidirectional"))
      (node (ref "USB") (pin "3") (pinfunction "D+_3") (pintype "passive"))
    )
    (net (code "9") (name "D-") (class "Default")
      (node (ref "U1") (pin "54") (pinfunction "D-_54") (pintype "bidirectional"))
      (node (ref "USB") (pin "2") (pinfunction "D-_2") (pintype "passive"))
    )
    (net (code "10") (name "E1_A") (class "Default")
      (node (ref "C39") (pin "1") (pinfunction "1_1") (pintype "passive"))
      (node (ref "KMW") (pin "6") (pinfunction "RA7_6") (pintype "bidirectional"))
      (node (ref "R26") (pin "1") (pinfunction "1_1") (pintype "passive"))
    )
    (net (code "11") (name "E1_B") (class "Default")
      (node (ref "C38") (pin "1") (pinfunction "1_1") (pintype "passive"))
      (node (ref "KMW") (pin "7") (pinfunction "RA6_7") (pintype "bidirectional"))
      (node (ref "R27") (pin "1") (pinfunction "1_1") (pintype "passive"))
    )
    (net (code "12") (name "E1_S") (class "Default")
      (node (ref "C40") (pin "1") (pinfunction "1_1") (pintype "passive"))
      (node (ref "KMW") (pin "4") (pinfunction "RA5_4") (pintype "bidirectional"))
      (node (ref "R24") (pin "2") (pinfunction "2_2") (pintype "passive"))
    )
    (net (code "13") (name "E2_A") (class "Default")
      (node (ref "C27") (pin "1") (pinfunction "1_1") (pintype "passive"))
      (node (ref "KMW") (pin "13") (pinfunction "RC5_13") (pintype "bidirectional"))
      (node (ref "R16") (pin "1") (pinfunction "1_1") (pintype "passive"))
    )
    (net (code "14") (name "E2_B") (class "Default")
      (node (ref "C26") (pin "1") (pinfunction "1_1") (pintype "passive"))
      (node (ref "KMW") (pin "14") (pinfunction "RC6_14") (pintype "bidirectional"))
      (node (ref "R17") (pin "1") (pinfunction "1_1") (pintype "passive"))
    )
    (net (code "15") (name "E2_S") (class "Default")
      (node (ref "C28") (pin "1") (pinfunction "1_1") (pintype "passive"))
      (node (ref "KMW") (pin "12") (pinfunction "RC4_12") (pintype "bidirectional"))
      (node (ref "R15") (pin "2") (pinfunction "2_2") (pintype "passive"))
    )
    (net (code "16") (name "EN_B") (class "Default")
      (node (ref "R46") (pin "1") (pinfunction "1_1") (pintype "passive"))
      (node (ref "U2") (pin "1") (pinfunction "EN_1") (pintype "input"))
    )
    (net (code "17") (name "G") (class "Default")
      (node (ref "KMW") (pin "28") (pinfunction "RA1_28") (pintype "bidirectional"))
      (node (ref "RGB") (pin "2") (pinfunction "GGND_2") (pintype "power_in"))
    )
    (net (code "18") (name "GND") (class "Default")
      (node (ref "B_GND") (pin "1") (pinfunction "P_1") (pintype "passive"))
      (node (ref "C10") (pin "2") (pinfunction "2_2") (pintype "passive"))
      (node (ref "C11") (pin "2") (pinfunction "2_2") (pintype "passive"))
      (node (ref "C12") (pin "2") (pinfunction "2_2") (pintype "passive"))
      (node (ref "C13") (pin "2") (pinfunction "2_2") (pintype "passive"))
      (node (ref "C14") (pin "2") (pinfunction "2_2") (pintype "passive"))
      (node (ref "C15") (pin "2") (pinfunction "2_2") (pintype "passive"))
      (node (ref "C16") (pin "2") (pinfunction "2_2") (pintype "passive"))
      (node (ref "C17") (pin "2") (pinfunction "2_2") (pintype "passive"))
      (node (ref "C18") (pin "2") (pinfunction "2_2") (pintype "passive"))
      (node (ref "C19") (pin "2") (pinfunction "2_2") (pintype "passive"))
      (node (ref "C21") (pin "2") (pinfunction "2_2") (pintype "passive"))
      (node (ref "C22") (pin "2") (pinfunction "2_2") (pintype "passive"))
      (node (ref "C23") (pin "2") (pinfunction "2_2") (pintype "passive"))
      (node (ref "C26") (pin "2") (pinfunction "2_2") (pintype "passive"))
      (node (ref "C27") (pin "2") (pinfunction "2_2") (pintype "passive"))
      (node (ref "C28") (pin "2") (pinfunction "2_2") (pintype "passive"))
      (node (ref "C29") (pin "2") (pinfunction "2_2") (pintype "passive"))
      (node (ref "C30") (pin "2") (pinfunction "2_2") (pintype "passive"))
      (node (ref "C31") (pin "2") (pinfunction "2_2") (pintype "passive"))
      (node (ref "C32") (pin "1") (pinfunction "1_1") (pintype "passive"))
      (node (ref "C33") (pin "1") (pinfunction "1_1") (pintype "passive"))
      (node (ref "C34") (pin "1") (pinfunction "1_1") (pintype "passive"))
      (node (ref "C35") (pin "1") (pinfunction "1_1") (pintype "passive"))
      (node (ref "C36") (pin "2") (pinfunction "2_2") (pintype "passive"))
      (node (ref "C37") (pin "2") (pinfunction "2_2") (pintype "passive"))
      (node (ref "C38") (pin "2") (pinfunction "2_2") (pintype "passive"))
      (node (ref "C39") (pin "2") (pinfunction "2_2") (pintype "passive"))
      (node (ref "C40") (pin "2") (pinfunction "2_2") (pintype "passive"))
      (node (ref "C41") (pin "1") (pinfunction "1_1") (pintype "passive"))
      (node (ref "C42") (pin "1") (pinfunction "1_1") (pintype "passive"))
      (node (ref "C43") (pin "2") (pinfunction "2_2") (pintype "passive"))
      (node (ref "C44") (pin "2") (pinfunction "2_2") (pintype "passive"))
      (node (ref "C45") (pin "1") (pinfunction "1_1") (pintype "passive"))
      (node (ref "C46") (pin "1") (pinfunction "1_1") (pintype "passive"))
      (node (ref "C47") (pin "1") (pinfunction "1_1") (pintype "passive"))
      (node (ref "C48") (pin "2") (pinfunction "2_2") (pintype "passive"))
      (node (ref "C49") (pin "2") (pinfunction "2_2") (pintype "passive"))
      (node (ref "C50") (pin "2") (pinfunction "2_2") (pintype "passive"))
      (node (ref "C51") (pin "2") (pinfunction "2_2") (pintype "passive"))
      (node (ref "C52") (pin "2") (pinfunction "2_2") (pintype "passive"))
      (node (ref "C53") (pin "2") (pinfunction "2_2") (pintype "passive"))
      (node (ref "C54") (pin "2") (pinfunction "2_2") (pintype "passive"))
      (node (ref "C55") (pin "2") (pinfunction "2_2") (pintype "passive"))
      (node (ref "C56") (pin "2") (pinfunction "2_2") (pintype "passive"))
      (node (ref "C57") (pin "2") (pinfunction "2_2") (pintype "passive"))
      (node (ref "C58") (pin "2") (pinfunction "2_2") (pintype "passive"))
      (node (ref "C59") (pin "2") (pinfunction "2_2") (pintype "passive"))
      (node (ref "C60") (pin "2") (pinfunction "2_2") (pintype "passive"))
      (node (ref "C_GND") (pin "1") (pinfunction "P_1") (pintype "passive"))
      (node (ref "E1") (pin "C") (pinfunction "C_C") (pintype "passive"))
      (node (ref "E1") (pin "E") (pinfunction "2_E") (pintype "passive"))
      (node (ref "E2") (pin "C") (pinfunction "C_C") (pintype "passive"))
      (node (ref "E2") (pin "E") (pinfunction "2_E") (pintype "passive"))
      (node (ref "E_GND") (pin "1") (pinfunction "P_1") (pintype "passive"))
      (node (ref "I2C") (pin "2") (pinfunction "2_2") (pintype "passive"))
      (node (ref "ICSP") (pin "3") (pinfunction "3_3") (pintype "passive"))
      (node (ref "JTAG") (pin "1") (pinfunction "1_1") (pintype "passive"))
      (node (ref "JTAG") (pin "11") (pinfunction "11_11") (pintype "passive"))
      (node (ref "JTAG") (pin "13") (pinfunction "13_13") (pintype "passive"))
      (node (ref "JTAG") (pin "3") (pinfunction "3_3") (pintype "passive"))
      (node (ref "JTAG") (pin "5") (pinfunction "5_5") (pintype "passive"))
      (node (ref "JTAG") (pin "7") (pinfunction "7_7") (pintype "passive"))
      (node (ref "JTAG") (pin "9") (pinfunction "9_9") (pintype "passive"))
      (node (ref "KME") (pin "16") (pinfunction "VSS_16") (pintype "power_in"))
      (node (ref "KME") (pin "5") (pinfunction "VSS_5") (pintype "power_in"))
      (node (ref "KME") (pin "EP") (pinfunction "EPAD_EP") (pintype "passive"))
      (node (ref "KMW") (pin "16") (pinfunction "VSS_16") (pintype "power_in"))
      (node (ref "KMW") (pin "5") (pinfunction "VSS_5") (pintype "power_in"))
      (node (ref "KMW") (pin "EP") (pinfunction "EPAD_EP") (pintype "passive"))
      (node (ref "LD1") (pin "C") (pinfunction "C_C") (pintype "passive"))
      (node (ref "LD2") (pin "C") (pinfunction "C_C") (pintype "passive"))
      (node (ref "P1") (pin "1") (pinfunction "1_1") (pintype "passive"))
      (node (ref "P10") (pin "4") (pinfunction "4_4") (pintype "passive"))
      (node (ref "P11") (pin "4") (pinfunction "4_4") (pintype "passive"))
      (node (ref "P12") (pin "4") (pinfunction "4_4") (pintype "passive"))
      (node (ref "P13") (pin "1") (pinfunction "1_1") (pintype "passive"))
      (node (ref "P2") (pin "1") (pinfunction "1_1") (pintype "passive"))
      (node (ref "P3") (pin "1") (pinfunction "1_1") (pintype "passive"))
      (node (ref "P4") (pin "3") (pinfunction "3_3") (pintype "passive"))
      (node (ref "P5") (pin "3") (pinfunction "3_3") (pintype "passive"))
      (node (ref "P6") (pin "3") (pinfunction "3_3") (pintype "passive"))
      (node (ref "P7") (pin "4") (pinfunction "4_4") (pintype "passive"))
      (node (ref "P8") (pin "4") (pinfunction "4_4") (pintype "passive"))
      (node (ref "P9") (pin "4") (pinfunction "4_4") (pintype "passive"))
      (node (ref "PWR") (pin "2") (pinfunction "2_2") (pintype "passive"))
      (node (ref "Q1") (pin "2") (pinfunction "S_2") (pintype "passive"))
      (node (ref "R47") (pin "1") (pinfunction "1_1") (pintype "passive"))
      (node (ref "R51") (pin "1") (pinfunction "1_1") (pintype "passive"))
      (node (ref "RESET") (pin "1") (pinfunction "1_1") (pintype "passive"))
      (node (ref "S1") (pin "1") (pinfunction "1_1") (pintype "passive"))
      (node (ref "S2") (pin "1") (pinfunction "1_1") (pintype "passive"))
      (node (ref "S3") (pin "1") (pinfunction "1_1") (pintype "passive"))
      (node (ref "S4") (pin "1") (pinfunction "1_1") (pintype "passive"))
      (node (ref "S5") (pin "1") (pinfunction "1_1") (pintype "passive"))
      (node (ref "S6") (pin "1") (pinfunction "1_1") (pintype "passive"))
      (node (ref "TFT") (pin "11") (pinfunction "VSYNC_11") (pintype "bidirectional"))
      (node (ref "TFT") (pin "12") (pinfunction "HSYNC_12") (pintype "bidirectional"))
      (node (ref "TFT") (pin "13") (pinfunction "DOTCLK_13") (pintype "bidirectional"))
      (node (ref "TFT") (pin "14") (pinfunction "DE_14") (pintype "bidirectional"))
      (node (ref "TFT") (pin "15") (pinfunction "DB17_15") (pintype "bidirectional"))
      (node (ref "TFT") (pin "16") (pinfunction "DB16_16") (pintype "bidirectional"))
      (node (ref "TFT") (pin "43") (pinfunction "GND_43") (pintype "bidirectional"))
      (node (ref "TFT") (pin "48") (pinfunction "GND_48") (pintype "bidirectional"))
      (node (ref "TFT") (pin "49") (pinfunction "GND_49") (pintype "bidirectional"))
      (node (ref "TFT") (pin "50") (pinfunction "GND_50") (pintype "bidirectional"))
      (node (ref "U1") (pin "13") (pinfunction "VSS_13") (pintype "power_in"))
      (node (ref "U1") (pin "31") (pinfunction "AVSS_31") (pintype "power_in"))
      (node (ref "U1") (pin "36") (pinfunction "VSS_36") (pintype "power_in"))
      (node (ref "U1") (pin "45") (pinfunction "VSS_45") (pintype "power_in"))
      (node (ref "U1") (pin "53") (pinfunction "VSS_53") (pintype "power_in"))
      (node (ref "U1") (pin "61") (pinfunction "PMA14_61") (pintype "bidirectional"))
      (node (ref "U1") (pin "63") (pinfunction "VSS_63") (pintype "power_in"))
      (node (ref "U1") (pin "75") (pinfunction "VSS_75") (pintype "power_in"))
      (node (ref "U1") (pin "84") (pinfunction "VSS_84") (pintype "power_in"))
      (node (ref "U1") (pin "92") (pinfunction "VSS_92") (pintype "power_in"))
      (node (ref "U2") (pin "5") (pinfunction "GND_5") (pintype "passive"))
      (node (ref "U2") (pin "6") (pinfunction "GND_6") (pintype "passive"))
      (node (ref "U2") (pin "EP") (pinfunction "GND_EP") (pintype "passive"))
      (node (ref "U3") (pin "2") (pinfunction "GND_2") (pintype "power_in"))
      (node (ref "UART") (pin "2") (pinfunction "2_2") (pintype "passive"))
      (node (ref "USB") (pin "5") (pinfunction "GND_5") (pintype "passive"))
      (node (ref "USB") (pin "Z1") (pinfunction "S1_Z1") (pintype "passive"))
      (node (ref "USB") (pin "Z2") (pinfunction "S2_Z2") (pintype "passive"))
      (node (ref "USB") (pin "Z3") (pinfunction "S2_Z3") (pintype "passive"))
      (node (ref "USB") (pin "Z4") (pinfunction "S1_Z4") (pintype "passive"))
      (node (ref "USB") (pin "Z5") (pinfunction "S3_Z5") (pintype "passive"))
      (node (ref "USB") (pin "Z6") (pinfunction "S3_Z6") (pintype "passive"))
      (node (ref "W_GND") (pin "1") (pinfunction "P_1") (pintype "passive"))
    )
    (net (code "19") (name "KME_PCLK") (class "Default")
      (node (ref "E_PCLK") (pin "TP") (pinfunction "TP_TP") (pintype "input"))
      (node (ref "KME") (pin "24") (pinfunction "RB6/ICSPCLK_24") (pintype "bidirectional"))
      (node (ref "U1") (pin "65") (pinfunction "PMA8_65") (pintype "bidirectional"))
    )
    (net (code "20") (name "KME_PDAT") (class "Default")
      (node (ref "E_PDAT") (pin "TP") (pinfunction "TP_TP") (pintype "input"))
      (node (ref "KME") (pin "25") (pinfunction "RB7/ICSPDAT_25") (pintype "bidirectional"))
      (node (ref "U1") (pin "64") (pinfunction "PMA9_64") (pintype "bidirectional"))
    )
    (net (code "21") (name "KME_~{MCLR}") (class "Default")
      (node (ref "E_!MCLR") (pin "TP") (pinfunction "TP_TP") (pintype "input"))
      (node (ref "KME") (pin "26") (pinfunction "RE3/~{MCLR}/VPP_26") (pintype "bidirectional"))
      (node (ref "U1") (pin "73") (pinfunction "SOSCO_73") (pintype "bidirectional"))
    )
    (net (code "22") (name "KMW_PCLK") (class "Default")
      (node (ref "KMW") (pin "24") (pinfunction "RB6/ICSPCLK_24") (pintype "bidirectional"))
      (node (ref "U1") (pin "58") (pinfunction "SCL3_58") (pintype "bidirectional"))
      (node (ref "W_PCLK") (pin "TP") (pinfunction "TP_TP") (pintype "input"))
    )
    (net (code "23") (name "KMW_PDAT") (class "Default")
      (node (ref "KMW") (pin "25") (pinfunction "RB7/ICSPDAT_25") (pintype "bidirectional"))
      (node (ref "U1") (pin "57") (pinfunction "SDA3_57") (pintype "bidirectional"))
      (node (ref "W_PDAT") (pin "TP") (pinfunction "TP_TP") (pintype "input"))
    )
    (net (code "24") (name "KMW_~{MCLR}") (class "Default")
      (node (ref "KMW") (pin "26") (pinfunction "RE3/~{MCLR}/VPP_26") (pintype "bidirectional"))
      (node (ref "U1") (pin "72") (pinfunction "SOSCI_72") (pintype "bidirectional"))
      (node (ref "W_!MCLR") (pin "TP") (pinfunction "TP_TP") (pintype "input"))
    )
    (net (code "25") (name "LED_A1") (class "Default")
      (node (ref "R41") (pin "2") (pinfunction "2_2") (pintype "passive"))
      (node (ref "TFT") (pin "2") (pinfunction "LEDA_2") (pintype "bidirectional"))
    )
    (net (code "26") (name "LED_A2") (class "Default")
      (node (ref "R42") (pin "2") (pinfunction "2_2") (pintype "passive"))
      (node (ref "TFT") (pin "3") (pinfunction "LEDA_3") (pintype "bidirectional"))
    )
    (net (code "27") (name "LED_A3") (class "Default")
      (node (ref "R43") (pin "2") (pinfunction "2_2") (pintype "passive"))
      (node (ref "TFT") (pin "4") (pinfunction "LEDA_4") (pintype "bidirectional"))
    )
    (net (code "28") (name "LED_A4") (class "Default")
      (node (ref "R44") (pin "2") (pinfunction "2_2") (pintype "passive"))
      (node (ref "TFT") (pin "5") (pinfunction "LEDA_5") (pintype "bidirectional"))
    )
    (net (code "29") (name "LED_CK") (class "Default")
      (node (ref "Q1") (pin "3") (pinfunction "D_3") (pintype "passive"))
      (node (ref "TFT") (pin "1") (pinfunction "LEDK_1") (pintype "bidirectional"))
    )
    (net (code "30") (name "Net-(B_P1-P)") (class "Default")
      (node (ref "B_P1") (pin "1") (pinfunction "P_1") (pintype "passive"))
      (node (ref "P1") (pin "4") (pinfunction "4_4") (pintype "passive"))
      (node (ref "R10") (pin "2") (pinfunction "2_2") (pintype "passive"))
    )
    (net (code "31") (name "Net-(B_P2-P)") (class "Default")
      (node (ref "B_P2") (pin "1") (pinfunction "P_1") (pintype "passive"))
      (node (ref "P2") (pin "4") (pinfunction "4_4") (pintype "passive"))
      (node (ref "R11") (pin "2") (pinfunction "2_2") (pintype "passive"))
    )
    (net (code "32") (name "Net-(B_P3-P)") (class "Default")
      (node (ref "B_P3") (pin "1") (pinfunction "P_1") (pintype "passive"))
      (node (ref "P3") (pin "4") (pinfunction "4_4") (pintype "passive"))
      (node (ref "R12") (pin "2") (pinfunction "2_2") (pintype "passive"))
    )
    (net (code "33") (name "Net-(B_P4-P)") (class "Default")
      (node (ref "B_P4") (pin "1") (pinfunction "P_1") (pintype "passive"))
      (node (ref "P4") (pin "2") (pinfunction "2_2") (pintype "passive"))
      (node (ref "R34") (pin "1") (pinfunction "1_1") (pintype "passive"))
    )
    (net (code "34") (name "Net-(B_P5-P)") (class "Default")
      (node (ref "B_P5") (pin "1") (pinfunction "P_1") (pintype "passive"))
      (node (ref "P5") (pin "2") (pinfunction "2_2") (pintype "passive"))
      (node (ref "R35") (pin "1") (pinfunction "1_1") (pintype "passive"))
    )
    (net (code "35") (name "Net-(B_P6-P)") (class "Default")
      (node (ref "B_P6") (pin "1") (pinfunction "P_1") (pintype "passive"))
      (node (ref "P6") (pin "2") (pinfunction "2_2") (pintype "passive"))
      (node (ref "R36") (pin "1") (pinfunction "1_1") (pintype "passive"))
    )
    (net (code "36") (name "Net-(B_P7-P)") (class "Default")
      (node (ref "B_P7") (pin "1") (pinfunction "P_1") (pintype "passive"))
      (node (ref "P7") (pin "1") (pinfunction "1_1") (pintype "passive"))
      (node (ref "R21") (pin "2") (pinfunction "2_2") (pintype "passive"))
    )
    (net (code "37") (name "Net-(B_P8-P)") (class "Default")
      (node (ref "B_P8") (pin "1") (pinfunction "P_1") (pintype "passive"))
      (node (ref "P8") (pin "1") (pinfunction "1_1") (pintype "passive"))
      (node (ref "R28") (pin "2") (pinfunction "2_2") (pintype "passive"))
    )
    (net (code "38") (name "Net-(B_P9-P)") (class "Default")
      (node (ref "B_P9") (pin "1") (pinfunction "P_1") (pintype "passive"))
      (node (ref "P9") (pin "1") (pinfunction "1_1") (pintype "passive"))
      (node (ref "R30") (pin "2") (pinfunction "2_2") (pintype "passive"))
    )
    (net (code "39") (name "Net-(B_P10-P)") (class "Default")
      (node (ref "B_P10") (pin "1") (pinfunction "P_1") (pintype "passive"))
      (node (ref "P10") (pin "1") (pinfunction "1_1") (pintype "passive"))
      (node (ref "R22") (pin "2") (pinfunction "2_2") (pintype "passive"))
    )
    (net (code "40") (name "Net-(B_P11-P)") (class "Default")
      (node (ref "B_P11") (pin "1") (pinfunction "P_1") (pintype "passive"))
      (node (ref "P11") (pin "1") (pinfunction "1_1") (pintype "passive"))
      (node (ref "R29") (pin "2") (pinfunction "2_2") (pintype "passive"))
    )
    (net (code "41") (name "Net-(B_P12-P)") (class "Default")
      (node (ref "B_P12") (pin "1") (pinfunction "P_1") (pintype "passive"))
      (node (ref "P12") (pin "1") (pinfunction "1_1") (pintype "passive"))
      (node (ref "R31") (pin "2") (pinfunction "2_2") (pintype "passive"))
    )
    (net (code "42") (name "Net-(B_P13-P)") (class "Default")
      (node (ref "B_P13") (pin "1") (pinfunction "P_1") (pintype "passive"))
      (node (ref "P13") (pin "4") (pinfunction "4_4") (pintype "passive"))
      (node (ref "R18") (pin "1") (pinfunction "1_1") (pintype "passive"))
    )
    (net (code "43") (name "Net-(E1D-1)") (class "Default")
      (node (ref "E1") (pin "D") (pinfunction "1_D") (pintype "passive"))
      (node (ref "E1_S") (pin "1") (pinfunction "P_1") (pintype "passive"))
      (node (ref "R24") (pin "1") (pinfunction "1_1") (pintype "passive"))
    )
    (net (code "44") (name "Net-(E1_A-P)") (class "Default")
      (node (ref "E1") (pin "A") (pinfunction "A_A") (pintype "passive"))
      (node (ref "E1_A") (pin "1") (pinfunction "P_1") (pintype "passive"))
      (node (ref "R26") (pin "2") (pinfunction "2_2") (pintype "passive"))
    )
    (net (code "45") (name "Net-(E1_B-P)") (class "Default")
      (node (ref "E1") (pin "B") (pinfunction "B_B") (pintype "passive"))
      (node (ref "E1_B") (pin "1") (pinfunction "P_1") (pintype "passive"))
      (node (ref "R27") (pin "2") (pinfunction "2_2") (pintype "passive"))
    )
    (net (code "46") (name "Net-(E2D-1)") (class "Default")
      (node (ref "E2") (pin "D") (pinfunction "1_D") (pintype "passive"))
      (node (ref "E2_S") (pin "1") (pinfunction "P_1") (pintype "passive"))
      (node (ref "R15") (pin "1") (pinfunction "1_1") (pintype "passive"))
    )
    (net (code "47") (name "Net-(E2_A-P)") (class "Default")
      (node (ref "E2") (pin "A") (pinfunction "A_A") (pintype "passive"))
      (node (ref "E2_A") (pin "1") (pinfunction "P_1") (pintype "passive"))
      (node (ref "R16") (pin "2") (pinfunction "2_2") (pintype "passive"))
    )
    (net (code "48") (name "Net-(E2_B-P)") (class "Default")
      (node (ref "E2") (pin "B") (pinfunction "B_B") (pintype "passive"))
      (node (ref "E2_B") (pin "1") (pinfunction "P_1") (pintype "passive"))
      (node (ref "R17") (pin "2") (pinfunction "2_2") (pintype "passive"))
    )
    (net (code "49") (name "Net-(E_RC0-P)") (class "Default")
      (node (ref "E_RC0") (pin "1") (pinfunction "P_1") (pintype "passive"))
      (node (ref "KME") (pin "8") (pinfunction "RC0_8") (pintype "bidirectional"))
    )
    (net (code "50") (name "Net-(E_RC1-P)") (class "Default")
      (node (ref "E_RC1") (pin "1") (pinfunction "P_1") (pintype "passive"))
      (node (ref "KME") (pin "9") (pinfunction "RC1_9") (pintype "bidirectional"))
    )
    (net (code "51") (name "Net-(KME-RA2)") (class "Default")
      (node (ref "KME") (pin "1") (pinfunction "RA2_1") (pintype "bidirectional"))
      (node (ref "TP1") (pin "TP") (pinfunction "TP_TP") (pintype "input"))
    )
    (net (code "52") (name "Net-(KME-RA5)") (class "Default")
      (node (ref "KME") (pin "4") (pinfunction "RA5_4") (pintype "bidirectional"))
      (node (ref "TP2") (pin "TP") (pinfunction "TP_TP") (pintype "input"))
    )
    (net (code "53") (name "Net-(KME-RA6)") (class "Default")
      (node (ref "KME") (pin "7") (pinfunction "RA6_7") (pintype "bidirectional"))
      (node (ref "TP3") (pin "TP") (pinfunction "TP_TP") (pintype "input"))
    )
    (net (code "54") (name "Net-(KMW-RC0)") (class "Default")
      (node (ref "KMW") (pin "8") (pinfunction "RC0_8") (pintype "bidirectional"))
      (node (ref "W_RC0") (pin "1") (pinfunction "P_1") (pintype "passive"))
    )
    (net (code "55") (name "Net-(KMW-RC1)") (class "Default")
      (node (ref "KMW") (pin "9") (pinfunction "RC1_9") (pintype "bidirectional"))
      (node (ref "W_RC1") (pin "1") (pinfunction "P_1") (pintype "passive"))
    )
    (net (code "56") (name "Net-(KMW-RC7)") (class "Default")
      (node (ref "KMW") (pin "15") (pinfunction "RC7_15") (pintype "bidirectional"))
      (node (ref "TP4") (pin "TP") (pinfunction "TP_TP") (pintype "input"))
    )
    (net (code "57") (name "Net-(LD1-PadA)") (class "Default")
      (node (ref "LD1") (pin "A") (pinfunction "A_A") (pintype "passive"))
      (node (ref "R13") (pin "2") (pinfunction "2_2") (pintype "passive"))
    )
    (net (code "58") (name "Net-(LD2-PadA)") (class "Default")
      (node (ref "LD2") (pin "A") (pinfunction "A_A") (pintype "passive"))
      (node (ref "R14") (pin "2") (pinfunction "2_2") (pintype "passive"))
    )
    (net (code "59") (name "Net-(Q1-G)") (class "Default")
      (node (ref "Q1") (pin "1") (pinfunction "G_1") (pintype "passive"))
      (node (ref "R40") (pin "1") (pinfunction "1_1") (pintype "passive"))
    )
    (net (code "60") (name "Net-(R19-Pad2)") (class "Default")
      (node (ref "R19") (pin "2") (pinfunction "2_2") (pintype "passive"))
      (node (ref "S3") (pin "2") (pinfunction "2_2") (pintype "passive"))
    )
    (net (code "61") (name "Net-(R20-Pad2)") (class "Default")
      (node (ref "R20") (pin "2") (pinfunction "2_2") (pintype "passive"))
      (node (ref "S4") (pin "2") (pinfunction "2_2") (pintype "passive"))
    )
    (net (code "62") (name "Net-(R23-Pad2)") (class "Default")
      (node (ref "R23") (pin "2") (pinfunction "2_2") (pintype "passive"))
      (node (ref "S1") (pin "2") (pinfunction "2_2") (pintype "passive"))
    )
    (net (code "63") (name "Net-(R25-Pad2)") (class "Default")
      (node (ref "R25") (pin "2") (pinfunction "2_2") (pintype "passive"))
      (node (ref "S2") (pin "2") (pinfunction "2_2") (pintype "passive"))
    )
    (net (code "64") (name "Net-(R32-Pad2)") (class "Default")
      (node (ref "R32") (pin "2") (pinfunction "2_2") (pintype "passive"))
      (node (ref "S5") (pin "2") (pinfunction "2_2") (pintype "passive"))
    )
    (net (code "65") (name "Net-(R33-Pad2)") (class "Default")
      (node (ref "R33") (pin "2") (pinfunction "2_2") (pintype "passive"))
      (node (ref "S6") (pin "2") (pinfunction "2_2") (pintype "passive"))
    )
    (net (code "66") (name "Net-(R48-Pad1)") (class "Default")
      (node (ref "R48") (pin "1") (pinfunction "1_1") (pintype "passive"))
      (node (ref "RESET") (pin "4") (pinfunction "4_4") (pintype "passive"))
    )
    (net (code "67") (name "Net-(RGB-BLUE)") (class "Default")
      (node (ref "R37") (pin "2") (pinfunction "2_2") (pintype "passive"))
      (node (ref "RGB") (pin "6") (pinfunction "BLUE_6") (pintype "bidirectional"))
    )
    (net (code "68") (name "Net-(RGB-GRN)") (class "Default")
      (node (ref "R38") (pin "2") (pinfunction "2_2") (pintype "passive"))
      (node (ref "RGB") (pin "5") (pinfunction "GRN_5") (pintype "bidirectional"))
    )
    (net (code "69") (name "Net-(RGB-RED)") (class "Default")
      (node (ref "R39") (pin "2") (pinfunction "2_2") (pintype "passive"))
      (node (ref "RGB") (pin "4") (pinfunction "RED_4") (pintype "bidirectional"))
    )
    (net (code "70") (name "Net-(U2-FB)") (class "Default")
      (node (ref "R45") (pin "1") (pinfunction "1_1") (pintype "passive"))
      (node (ref "R47") (pin "2") (pinfunction "2_2") (pintype "passive"))
      (node (ref "U2") (pin "7") (pinfunction "FB_7") (pintype "output"))
    )
    (net (code "71") (name "OEN") (class "Default")
      (node (ref "U1") (pin "50") (pinfunction "OSC2_50") (pintype "bidirectional"))
    )
    (net (code "72") (name "OSC1") (class "Default")
      (node (ref "U1") (pin "49") (pinfunction "OSC1_49") (pintype "bidirectional"))
      (node (ref "U3") (pin "3") (pinfunction "OUT_3") (pintype "output"))
    )
    (net (code "73") (name "P1") (class "Default")
      (node (ref "C21") (pin "1") (pinfunction "1_1") (pintype "passive"))
      (node (ref "KME") (pin "21") (pinfunction "RB3_21") (pintype "bidirectional"))
      (node (ref "R10") (pin "1") (pinfunction "1_1") (pintype "passive"))
    )
    (net (code "74") (name "P2") (class "Default")
      (node (ref "C22") (pin "1") (pinfunction "1_1") (pintype "passive"))
      (node (ref "KME") (pin "22") (pinfunction "RB4_22") (pintype "bidirectional"))
      (node (ref "R11") (pin "1") (pinfunction "1_1") (pintype "passive"))
    )
    (net (code "75") (name "P3") (class "Default")
      (node (ref "C23") (pin "1") (pinfunction "1_1") (pintype "passive"))
      (node (ref "KME") (pin "23") (pinfunction "RB5_23") (pintype "bidirectional"))
      (node (ref "R12") (pin "1") (pinfunction "1_1") (pintype "passive"))
    )
    (net (code "76") (name "P4") (class "Default")
      (node (ref "C45") (pin "2") (pinfunction "2_2") (pintype "passive"))
      (node (ref "KME") (pin "15") (pinfunction "RC7_15") (pintype "bidirectional"))
      (node (ref "R34") (pin "2") (pinfunction "2_2") (pintype "passive"))
    )
    (net (code "77") (name "P5") (class "Default")
      (node (ref "C46") (pin "2") (pinfunction "2_2") (pintype "passive"))
      (node (ref "KME") (pin "14") (pinfunction "RC6_14") (pintype "bidirectional"))
      (node (ref "R35") (pin "2") (pinfunction "2_2") (pintype "passive"))
    )
    (net (code "78") (name "P6") (class "Default")
      (node (ref "C47") (pin "2") (pinfunction "2_2") (pintype "passive"))
      (node (ref "KME") (pin "13") (pinfunction "RC5_13") (pintype "bidirectional"))
      (node (ref "R36") (pin "2") (pinfunction "2_2") (pintype "passive"))
    )
    (net (code "79") (name "P7") (class "Default")
      (node (ref "C32") (pin "2") (pinfunction "2_2") (pintype "passive"))
      (node (ref "KME") (pin "12") (pinfunction "RC4_12") (pintype "bidirectional"))
      (node (ref "R21") (pin "1") (pinfunction "1_1") (pintype "passive"))
    )
    (net (code "80") (name "P8") (class "Default")
      (node (ref "C34") (pin "2") (pinfunction "2_2") (pintype "passive"))
      (node (ref "KME") (pin "11") (pinfunction "RC3_11") (pintype "bidirectional"))
      (node (ref "R28") (pin "1") (pinfunction "1_1") (pintype "passive"))
    )
    (net (code "81") (name "P9") (class "Default")
      (node (ref "C41") (pin "2") (pinfunction "2_2") (pintype "passive"))
      (node (ref "KME") (pin "10") (pinfunction "RC2_10") (pintype "bidirectional"))
      (node (ref "R30") (pin "1") (pinfunction "1_1") (pintype "passive"))
    )
    (net (code "82") (name "P10") (class "Default")
      (node (ref "C33") (pin "2") (pinfunction "2_2") (pintype "passive"))
      (node (ref "KME") (pin "20") (pinfunction "RB2_20") (pintype "bidirectional"))
      (node (ref "R22") (pin "1") (pinfunction "1_1") (pintype "passive"))
    )
    (net (code "83") (name "P11") (class "Default")
      (node (ref "C35") (pin "2") (pinfunction "2_2") (pintype "passive"))
      (node (ref "KME") (pin "19") (pinfunction "RB1_19") (pintype "bidirectional"))
      (node (ref "R29") (pin "1") (pinfunction "1_1") (pintype "passive"))
    )
    (net (code "84") (name "P12") (class "Default")
      (node (ref "C42") (pin "2") (pinfunction "2_2") (pintype "passive"))
      (node (ref "KME") (pin "18") (pinfunction "RB0_18") (pintype "bidirectional"))
      (node (ref "R31") (pin "1") (pinfunction "1_1") (pintype "passive"))
    )
    (net (code "85") (name "P13") (class "Default")
      (node (ref "C29") (pin "1") (pinfunction "1_1") (pintype "passive"))
      (node (ref "KMW") (pin "23") (pinfunction "RB5_23") (pintype "bidirectional"))
      (node (ref "R18") (pin "2") (pinfunction "2_2") (pintype "passive"))
    )
    (net (code "86") (name "PGEC1") (class "Default")
      (node (ref "ICSP") (pin "5") (pinfunction "5_5") (pintype "passive"))
      (node (ref "PGEC") (pin "1") (pinfunction "P_1") (pintype "passive"))
      (node (ref "U1") (pin "24") (pinfunction "RB1_24") (pintype "bidirectional"))
    )
    (net (code "87") (name "PGED1") (class "Default")
      (node (ref "ICSP") (pin "4") (pinfunction "4_4") (pintype "passive"))
      (node (ref "PGED") (pin "1") (pinfunction "P_1") (pintype "passive"))
      (node (ref "U1") (pin "25") (pinfunction "RB0_25") (pintype "bidirectional"))
    )
    (net (code "88") (name "PMD0") (class "Default")
      (node (ref "TFT") (pin "32") (pinfunction "DB0_32") (pintype "bidirectional"))
      (node (ref "U1") (pin "91") (pinfunction "PMD0_91") (pintype "bidirectional"))
    )
    (net (code "89") (name "PMD1") (class "Default")
      (node (ref "TFT") (pin "31") (pinfunction "DB1_31") (pintype "bidirectional"))
      (node (ref "U1") (pin "94") (pinfunction "PMD1_94") (pintype "bidirectional"))
    )
    (net (code "90") (name "PMD2") (class "Default")
      (node (ref "TFT") (pin "30") (pinfunction "DB2_30") (pintype "bidirectional"))
      (node (ref "U1") (pin "98") (pinfunction "PMD2_98") (pintype "bidirectional"))
    )
    (net (code "91") (name "PMD3") (class "Default")
      (node (ref "TFT") (pin "29") (pinfunction "DB3_29") (pintype "bidirectional"))
      (node (ref "U1") (pin "99") (pinfunction "PMD3_99") (pintype "bidirectional"))
    )
    (net (code "92") (name "PMD4") (class "Default")
      (node (ref "TFT") (pin "28") (pinfunction "DB4_28") (pintype "bidirectional"))
      (node (ref "U1") (pin "100") (pinfunction "PMD4_100") (pintype "bidirectional"))
    )
    (net (code "93") (name "PMD5") (class "Default")
      (node (ref "TFT") (pin "27") (pinfunction "DB5_27") (pintype "bidirectional"))
      (node (ref "U1") (pin "3") (pinfunction "PMD5_3") (pintype "bidirectional"))
    )
    (net (code "94") (name "PMD6") (class "Default")
      (node (ref "TFT") (pin "26") (pinfunction "DB6_26") (pintype "bidirectional"))
      (node (ref "U1") (pin "4") (pinfunction "PMD6_4") (pintype "bidirectional"))
    )
    (net (code "95") (name "PMD7") (class "Default")
      (node (ref "TFT") (pin "25") (pinfunction "DB7_25") (pintype "bidirectional"))
      (node (ref "U1") (pin "5") (pinfunction "PMD7_5") (pintype "bidirectional"))
    )
    (net (code "96") (name "PMD8") (class "Default")
      (node (ref "TFT") (pin "24") (pinfunction "DB8_24") (pintype "bidirectional"))
      (node (ref "U1") (pin "88") (pinfunction "PMD8_88") (pintype "bidirectional"))
    )
    (net (code "97") (name "PMD9") (class "Default")
      (node (ref "TFT") (pin "23") (pinfunction "DB9_23") (pintype "bidirectional"))
      (node (ref "U1") (pin "87") (pinfunction "PMD9_87") (pintype "bidirectional"))
    )
    (net (code "98") (name "PMD10") (class "Default")
      (node (ref "TFT") (pin "22") (pinfunction "DB10_22") (pintype "bidirectional"))
      (node (ref "U1") (pin "86") (pinfunction "PMD10_86") (pintype "bidirectional"))
    )
    (net (code "99") (name "PMD11") (class "Default")
      (node (ref "TFT") (pin "21") (pinfunction "DB11_21") (pintype "bidirectional"))
      (node (ref "U1") (pin "85") (pinfunction "PMD11_85") (pintype "bidirectional"))
    )
    (net (code "100") (name "PMD12") (class "Default")
      (node (ref "TFT") (pin "20") (pinfunction "DB12_20") (pintype "bidirectional"))
      (node (ref "U1") (pin "79") (pinfunction "PMD12_79") (pintype "bidirectional"))
    )
    (net (code "101") (name "PMD13") (class "Default")
      (node (ref "TFT") (pin "19") (pinfunction "DB13_19") (pintype "bidirectional"))
      (node (ref "U1") (pin "80") (pinfunction "PMD13_80") (pintype "bidirectional"))
    )
    (net (code "102") (name "PMD14") (class "Default")
      (node (ref "TFT") (pin "18") (pinfunction "DB14_18") (pintype "bidirectional"))
      (node (ref "U1") (pin "77") (pinfunction "PMD14_77") (pintype "bidirectional"))
    )
    (net (code "103") (name "PMD15") (class "Default")
      (node (ref "TFT") (pin "17") (pinfunction "DB15_17") (pintype "bidirectional"))
      (node (ref "U1") (pin "78") (pinfunction "PMD15_78") (pintype "bidirectional"))
    )
    (net (code "104") (name "PMRD") (class "Default")
      (node (ref "TFT") (pin "35") (pinfunction "/RD_35") (pintype "bidirectional"))
      (node (ref "U1") (pin "9") (pinfunction "PMRD_9") (pintype "bidirectional"))
    )
    (net (code "105") (name "PMWR") (class "Default")
      (node (ref "TFT") (pin "36") (pinfunction "/WR_RS_36") (pintype "bidirectional"))
      (node (ref "U1") (pin "8") (pinfunction "PMWR_8") (pintype "bidirectional"))
    )
    (net (code "106") (name "R") (class "Default")
      (node (ref "KMW") (pin "1") (pinfunction "RA2_1") (pintype "bidirectional"))
      (node (ref "RGB") (pin "3") (pinfunction "RGND_3") (pintype "power_in"))
    )
    (net (code "107") (name "RA5") (class "Default")
      (node (ref "TFT") (pin "47") (pinfunction "TP_RES_47") (pintype "bidirectional"))
      (node (ref "U1") (pin "2") (pinfunction "PMA5_2") (pintype "bidirectional"))
    )
    (net (code "108") (name "RA6") (class "Default")
      (node (ref "U1") (pin "89") (pinfunction "SQICLK_89") (pintype "bidirectional"))
    )
    (net (code "109") (name "RA7") (class "Default")
      (node (ref "U1") (pin "90") (pinfunction "SQID3_90") (pintype "bidirectional"))
    )
    (net (code "110") (name "RA9") (class "Default")
      (node (ref "U1") (pin "28") (pinfunction "RA9_28") (pintype "bidirectional"))
    )
    (net (code "111") (name "RA10") (class "Default")
      (node (ref "U1") (pin "29") (pinfunction "RA10_29") (pintype "bidirectional"))
    )
    (net (code "112") (name "RB4") (class "Default")
      (node (ref "U1") (pin "21") (pinfunction "RB4_21") (pintype "bidirectional"))
    )
    (net (code "113") (name "RB12") (class "Default")
      (node (ref "TFT") (pin "9") (pinfunction "IM3_9") (pintype "bidirectional"))
      (node (ref "U1") (pin "41") (pinfunction "PMA11_41") (pintype "bidirectional"))
    )
    (net (code "114") (name "RB13") (class "Default")
      (node (ref "TFT") (pin "8") (pinfunction "IM2_8") (pintype "bidirectional"))
      (node (ref "U1") (pin "42") (pinfunction "RB13_42") (pintype "bidirectional"))
    )
    (net (code "115") (name "RD1") (class "Default")
      (node (ref "U1") (pin "76") (pinfunction "SCK1_76") (pintype "bidirectional"))
    )
    (net (code "116") (name "RG12") (class "Default")
      (node (ref "U1") (pin "96") (pinfunction "SQID1_96") (pintype "bidirectional"))
    )
    (net (code "117") (name "RG13") (class "Default")
      (node (ref "U1") (pin "97") (pinfunction "SQID0_97") (pintype "bidirectional"))
    )
    (net (code "118") (name "RG14") (class "Default")
      (node (ref "U1") (pin "95") (pinfunction "SQID2_95") (pintype "bidirectional"))
    )
    (net (code "119") (name "RG15") (class "Default")
      (node (ref "TFT") (pin "39") (pinfunction "TE_39") (pintype "bidirectional"))
      (node (ref "U1") (pin "1") (pinfunction "RG15_1") (pintype "bidirectional"))
    )
    (net (code "120") (name "RPB2{slash}4RX{slash}6RX{slash}SS2{slash}SDI6") (class "Default")
      (node (ref "U1") (pin "23") (pinfunction "RB2_23") (pintype "bidirectional"))
    )
    (net (code "121") (name "RPB3{slash}3RX{slash}SDI2{slash}SDI4") (class "Default")
      (node (ref "U1") (pin "22") (pinfunction "RB3_22") (pintype "bidirectional"))
    )
    (net (code "122") (name "RPB5") (class "Default")
      (node (ref "ICSP") (pin "6") (pinfunction "6_6") (pintype "passive"))
      (node (ref "U1") (pin "20") (pinfunction "RB5_20") (pintype "bidirectional"))
    )
    (net (code "123") (name "RPB6{slash}4RX{slash}6RX{slash}SS2{slash}SDI6") (class "Default")
      (node (ref "U1") (pin "26") (pinfunction "RB6_26") (pintype "bidirectional"))
    )
    (net (code "124") (name "RPB7{slash}2RX{slash}SS1{slash}SS3-SS5") (class "Default")
      (node (ref "U1") (pin "27") (pinfunction "RB7_27") (pintype "bidirectional"))
    )
    (net (code "125") (name "RPB8{slash}2RX{slash}SS1{slash}SS3-SS5") (class "Default")
      (node (ref "U1") (pin "32") (pinfunction "PMA10_32") (pintype "bidirectional"))
    )
    (net (code "126") (name "RPB9{slash}1RX{slash}5RX{slash}SDI1{slash}SDI3{slash}SDI5{slash}SS6") (class "Default")
      (node (ref "U1") (pin "33") (pinfunction "PMA7_33") (pintype "bidirectional"))
    )
    (net (code "127") (name "RPB10{slash}1RX{slash}5RX{slash}SDI1{slash}SDI3{slash}SDI5{slash}SS6") (class "Default")
      (node (ref "U1") (pin "34") (pinfunction "PMA13_34") (pintype "bidirectional"))
    )
    (net (code "128") (name "RPB14") (class "Default")
      (node (ref "TFT") (pin "7") (pinfunction "IM1_7") (pintype "bidirectional"))
      (node (ref "U1") (pin "43") (pinfunction "PMA1_43") (pintype "bidirectional"))
    )
    (net (code "129") (name "RPB15") (class "Default")
      (node (ref "TFT") (pin "6") (pinfunction "IM0_6") (pintype "bidirectional"))
      (node (ref "U1") (pin "44") (pinfunction "PMA0_44") (pintype "bidirectional"))
    )
    (net (code "130") (name "RPD0") (class "Default")
      (node (ref "U1") (pin "71") (pinfunction "RTCC_71") (pintype "bidirectional"))
    )
    (net (code "131") (name "RPD4") (class "Default")
      (node (ref "U1") (pin "81") (pinfunction "SQICS0_81") (pintype "bidirectional"))
    )
    (net (code "132") (name "RPD5") (class "Default")
      (node (ref "U1") (pin "82") (pinfunction "SQICS1_82") (pintype "bidirectional"))
    )
    (net (code "133") (name "RPD10") (class "Default")
      (node (ref "R40") (pin "2") (pinfunction "2_2") (pintype "passive"))
      (node (ref "U1") (pin "69") (pinfunction "SCK4_69") (pintype "bidirectional"))
    )
    (net (code "134") (name "RPD11") (class "Default")
      (node (ref "TFT") (pin "10") (pinfunction "/RESET_10") (pintype "bidirectional"))
      (node (ref "U1") (pin "70") (pinfunction "RD11_70") (pintype "bidirectional"))
    )
    (net (code "135") (name "RPD15") (class "Default")
      (node (ref "U1") (pin "47") (pinfunction "RD14_47") (pintype "bidirectional"))
    )
    (net (code "136") (name "RPE8") (class "Default")
      (node (ref "U1") (pin "18") (pinfunction "RE8_18") (pintype "bidirectional"))
      (node (ref "UART") (pin "3") (pinfunction "3_3") (pintype "passive"))
    )
    (net (code "137") (name "RPE9") (class "Default")
      (node (ref "U1") (pin "19") (pinfunction "RE9_19") (pintype "bidirectional"))
      (node (ref "UART") (pin "1") (pinfunction "1_1") (pintype "passive"))
    )
    (net (code "138") (name "RPG9") (class "Default")
      (node (ref "TFT") (pin "46") (pinfunction "TP_IRQ_46") (pintype "bidirectional"))
      (node (ref "U1") (pin "16") (pinfunction "PMA2_16") (pintype "bidirectional"))
    )
    (net (code "139") (name "S1_A") (class "Default")
      (node (ref "C44") (pin "1") (pinfunction "1_1") (pintype "passive"))
      (node (ref "KMW") (pin "3") (pinfunction "RA4_3") (pintype "bidirectional"))
      (node (ref "R32") (pin "1") (pinfunction "1_1") (pintype "passive"))
    )
    (net (code "140") (name "S1_B") (class "Default")
      (node (ref "C43") (pin "1") (pinfunction "1_1") (pintype "passive"))
      (node (ref "KMW") (pin "2") (pinfunction "RA3_2") (pintype "bidirectional"))
      (node (ref "R33") (pin "1") (pinfunction "1_1") (pintype "passive"))
    )
    (net (code "141") (name "S2_A") (class "Default")
      (node (ref "KME") (pin "28") (pinfunction "RA1_28") (pintype "bidirectional"))
      (node (ref "R13") (pin "1") (pinfunction "1_1") (pintype "passive"))
    )
    (net (code "142") (name "S2_B") (class "Default")
      (node (ref "KME") (pin "27") (pinfunction "RA0_27") (pintype "bidirectional"))
      (node (ref "R14") (pin "1") (pinfunction "1_1") (pintype "passive"))
    )
    (net (code "143") (name "SCK6") (class "Default")
      (node (ref "TFT") (pin "37") (pinfunction "RS_SCL_37") (pintype "bidirectional"))
      (node (ref "U1") (pin "48") (pinfunction "RD15_48") (pintype "bidirectional"))
    )
    (net (code "144") (name "SCL1") (class "Default")
      (node (ref "TFT") (pin "44") (pinfunction "TP_SCK_44") (pintype "bidirectional"))
      (node (ref "U1") (pin "66") (pinfunction "SCL1_66") (pintype "bidirectional"))
    )
    (net (code "145") (name "SCL2") (class "Default")
      (node (ref "U1") (pin "59") (pinfunction "SCL2_59") (pintype "bidirectional"))
    )
    (net (code "146") (name "SCL4") (class "Default")
      (node (ref "I2C") (pin "1") (pinfunction "1_1") (pintype "passive"))
      (node (ref "U1") (pin "12") (pinfunction "PMA3_12") (pintype "bidirectional"))
    )
    (net (code "147") (name "SDA1") (class "Default")
      (node (ref "TFT") (pin "45") (pinfunction "TP_SDA_45") (pintype "bidirectional"))
      (node (ref "U1") (pin "67") (pinfunction "SDA1_67") (pintype "bidirectional"))
    )
    (net (code "148") (name "SDA2") (class "Default")
      (node (ref "U1") (pin "60") (pinfunction "SDA2_60") (pintype "bidirectional"))
    )
    (net (code "149") (name "SDA4") (class "Default")
      (node (ref "I2C") (pin "3") (pinfunction "3_3") (pintype "passive"))
      (node (ref "U1") (pin "11") (pinfunction "PMA4_11") (pintype "bidirectional"))
    )
    (net (code "150") (name "SDI6") (class "Default")
      (node (ref "TFT") (pin "33") (pinfunction "SDO_33") (pintype "bidirectional"))
      (node (ref "U1") (pin "7") (pinfunction "PMA12_7") (pintype "bidirectional"))
    )
    (net (code "151") (name "SDO6") (class "Default")
      (node (ref "TFT") (pin "34") (pinfunction "SDI_34") (pintype "bidirectional"))
      (node (ref "U1") (pin "10") (pinfunction "RG6_10") (pintype "bidirectional"))
    )
    (net (code "152") (name "TCK") (class "Default")
      (node (ref "JTAG") (pin "6") (pinfunction "6_6") (pintype "passive"))
      (node (ref "U1") (pin "38") (pinfunction "TCK_38") (pintype "bidirectional"))
    )
    (net (code "153") (name "TDI") (class "Default")
      (node (ref "JTAG") (pin "10") (pinfunction "10_10") (pintype "passive"))
      (node (ref "U1") (pin "39") (pinfunction "TDI_39") (pintype "bidirectional"))
    )
    (net (code "154") (name "TDO") (class "Default")
      (node (ref "JTAG") (pin "8") (pinfunction "8_8") (pintype "passive"))
      (node (ref "U1") (pin "40") (pinfunction "TDO_40") (pintype "bidirectional"))
    )
    (net (code "155") (name "TMS") (class "Default")
      (node (ref "JTAG") (pin "4") (pinfunction "4_4") (pintype "passive"))
      (node (ref "U1") (pin "17") (pinfunction "TMS_17") (pintype "bidirectional"))
    )
    (net (code "156") (name "TS1_A") (class "Default")
      (node (ref "C37") (pin "1") (pinfunction "1_1") (pintype "passive"))
      (node (ref "KMW") (pin "20") (pinfunction "RB2_20") (pintype "bidirectional"))
      (node (ref "R23") (pin "1") (pinfunction "1_1") (pintype "passive"))
    )
    (net (code "157") (name "TS1_B") (class "Default")
      (node (ref "C36") (pin "1") (pinfunction "1_1") (pintype "passive"))
      (node (ref "KMW") (pin "21") (pinfunction "RB3_21") (pintype "bidirectional"))
      (node (ref "R25") (pin "1") (pinfunction "1_1") (pintype "passive"))
    )
    (net (code "158") (name "TS2_A") (class "Default")
      (node (ref "C31") (pin "1") (pinfunction "1_1") (pintype "passive"))
      (node (ref "KMW") (pin "10") (pinfunction "RC2_10") (pintype "bidirectional"))
      (node (ref "R19") (pin "1") (pinfunction "1_1") (pintype "passive"))
    )
    (net (code "159") (name "TS2_B") (class "Default")
      (node (ref "C30") (pin "1") (pinfunction "1_1") (pintype "passive"))
      (node (ref "KMW") (pin "11") (pinfunction "RC3_11") (pintype "bidirectional"))
      (node (ref "R20") (pin "1") (pinfunction "1_1") (pintype "passive"))
    )
    (net (code "160") (name "USBID") (class "Default")
      (node (ref "U1") (pin "56") (pinfunction "USBID_56") (pintype "bidirectional"))
      (node (ref "USB") (pin "4") (pinfunction "ID_4") (pintype "passive"))
    )
    (net (code "161") (name "VBUS") (class "Default")
      (node (ref "D1") (pin "A") (pinfunction "A_A") (pintype "passive"))
      (node (ref "U1") (pin "51") (pinfunction "VBUS_51") (pintype "power_in"))
      (node (ref "USB") (pin "1") (pinfunction "VBUS_1") (pintype "passive"))
    )
    (net (code "162") (name "VOUT_B") (class "Default")
      (node (ref "C53") (pin "1") (pinfunction "1_1") (pintype "passive"))
      (node (ref "FB2") (pin "1") (pinfunction "1_1") (pintype "passive"))
      (node (ref "R45") (pin "2") (pinfunction "2_2") (pintype "passive"))
      (node (ref "U2") (pin "8") (pinfunction "VOUT_8") (pintype "output"))
    )
    (net (code "163") (name "unconnected-(JTAG-Pad12)") (class "Default")
      (node (ref "JTAG") (pin "12") (pinfunction "12_12") (pintype "passive"))
    )
    (net (code "164") (name "unconnected-(JTAG-Pad14)") (class "Default")
      (node (ref "JTAG") (pin "14") (pinfunction "14_14") (pintype "passive"))
    )
    (net (code "165") (name "unconnected-(KME-RA3-Pad2)") (class "Default")
      (node (ref "KME") (pin "2") (pinfunction "RA3_2") (pintype "bidirectional"))
    )
    (net (code "166") (name "unconnected-(KME-RA4-Pad3)") (class "Default")
      (node (ref "KME") (pin "3") (pinfunction "RA4_3") (pintype "bidirectional"))
    )
    (net (code "167") (name "unconnected-(KME-RA7-Pad6)") (class "Default")
      (node (ref "KME") (pin "6") (pinfunction "RA7_6") (pintype "bidirectional"))
    )
    (net (code "168") (name "unconnected-(KMW-RB0-Pad18)") (class "Default")
      (node (ref "KMW") (pin "18") (pinfunction "RB0_18") (pintype "bidirectional"))
    )
    (net (code "169") (name "unconnected-(KMW-RB1-Pad19)") (class "Default")
      (node (ref "KMW") (pin "19") (pinfunction "RB1_19") (pintype "bidirectional"))
    )
    (net (code "170") (name "unconnected-(KMW-RB4-Pad22)") (class "Default")
      (node (ref "KMW") (pin "22") (pinfunction "RB4_22") (pintype "bidirectional"))
    )
    (net (code "171") (name "unconnected-(P1-Pad2)") (class "Default")
      (node (ref "P1") (pin "2") (pinfunction "2_2") (pintype "passive"))
    )
    (net (code "172") (name "unconnected-(P1-Pad3)") (class "Default")
      (node (ref "P1") (pin "3") (pinfunction "3_3") (pintype "passive"))
    )
    (net (code "173") (name "unconnected-(P2-Pad2)") (class "Default")
      (node (ref "P2") (pin "2") (pinfunction "2_2") (pintype "passive"))
    )
    (net (code "174") (name "unconnected-(P2-Pad3)") (class "Default")
      (node (ref "P2") (pin "3") (pinfunction "3_3") (pintype "passive"))
    )
    (net (code "175") (name "unconnected-(P3-Pad2)") (class "Default")
      (node (ref "P3") (pin "2") (pinfunction "2_2") (pintype "passive"))
    )
    (net (code "176") (name "unconnected-(P3-Pad3)") (class "Default")
      (node (ref "P3") (pin "3") (pinfunction "3_3") (pintype "passive"))
    )
    (net (code "177") (name "unconnected-(P4-Pad1)") (class "Default")
      (node (ref "P4") (pin "1") (pinfunction "1_1") (pintype "passive"))
    )
    (net (code "178") (name "unconnected-(P4-Pad4)") (class "Default")
      (node (ref "P4") (pin "4") (pinfunction "4_4") (pintype "passive"))
    )
    (net (code "179") (name "unconnected-(P5-Pad1)") (class "Default")
      (node (ref "P5") (pin "1") (pinfunction "1_1") (pintype "passive"))
    )
    (net (code "180") (name "unconnected-(P5-Pad4)") (class "Default")
      (node (ref "P5") (pin "4") (pinfunction "4_4") (pintype "passive"))
    )
    (net (code "181") (name "unconnected-(P6-Pad1)") (class "Default")
      (node (ref "P6") (pin "1") (pinfunction "1_1") (pintype "passive"))
    )
    (net (code "182") (name "unconnected-(P6-Pad4)") (class "Default")
      (node (ref "P6") (pin "4") (pinfunction "4_4") (pintype "passive"))
    )
    (net (code "183") (name "unconnected-(P7-Pad2)") (class "Default")
      (node (ref "P7") (pin "2") (pinfunction "2_2") (pintype "passive"))
    )
    (net (code "184") (name "unconnected-(P7-Pad3)") (class "Default")
      (node (ref "P7") (pin "3") (pinfunction "3_3") (pintype "passive"))
    )
    (net (code "185") (name "unconnected-(P8-Pad2)") (class "Default")
      (node (ref "P8") (pin "2") (pinfunction "2_2") (pintype "passive"))
    )
    (net (code "186") (name "unconnected-(P8-Pad3)") (class "Default")
      (node (ref "P8") (pin "3") (pinfunction "3_3") (pintype "passive"))
    )
    (net (code "187") (name "unconnected-(P9-Pad2)") (class "Default")
      (node (ref "P9") (pin "2") (pinfunction "2_2") (pintype "passive"))
    )
    (net (code "188") (name "unconnected-(P9-Pad3)") (class "Default")
      (node (ref "P9") (pin "3") (pinfunction "3_3") (pintype "passive"))
    )
    (net (code "189") (name "unconnected-(P10-Pad2)") (class "Default")
      (node (ref "P10") (pin "2") (pinfunction "2_2") (pintype "passive"))
    )
    (net (code "190") (name "unconnected-(P10-Pad3)") (class "Default")
      (node (ref "P10") (pin "3") (pinfunction "3_3") (pintype "passive"))
    )
    (net (code "191") (name "unconnected-(P11-Pad2)") (class "Default")
      (node (ref "P11") (pin "2") (pinfunction "2_2") (pintype "passive"))
    )
    (net (code "192") (name "unconnected-(P11-Pad3)") (class "Default")
      (node (ref "P11") (pin "3") (pinfunction "3_3") (pintype "passive"))
    )
    (net (code "193") (name "unconnected-(P12-Pad2)") (class "Default")
      (node (ref "P12") (pin "2") (pinfunction "2_2") (pintype "passive"))
    )
    (net (code "194") (name "unconnected-(P12-Pad3)") (class "Default")
      (node (ref "P12") (pin "3") (pinfunction "3_3") (pintype "passive"))
    )
    (net (code "195") (name "unconnected-(P13-Pad2)") (class "Default")
      (node (ref "P13") (pin "2") (pinfunction "2_2") (pintype "passive"))
    )
    (net (code "196") (name "unconnected-(P13-Pad3)") (class "Default")
      (node (ref "P13") (pin "3") (pinfunction "3_3") (pintype "passive"))
    )
    (net (code "197") (name "unconnected-(RESET-Pad2)") (class "Default")
      (node (ref "RESET") (pin "2") (pinfunction "2_2") (pintype "passive"))
    )
    (net (code "198") (name "unconnected-(RESET-Pad3)") (class "Default")
      (node (ref "RESET") (pin "3") (pinfunction "3_3") (pintype "passive"))
    )
    (net (code "199") (name "~{MCLR}") (class "Default")
      (node (ref "!MCLR") (pin "1") (pinfunction "P_1") (pintype "passive"))
      (node (ref "C54") (pin "1") (pinfunction "1_1") (pintype "passive"))
      (node (ref "ICSP") (pin "1") (pinfunction "1_1") (pintype "passive"))
      (node (ref "R48") (pin "2") (pinfunction "2_2") (pintype "passive"))
      (node (ref "R49") (pin "1") (pinfunction "1_1") (pintype "passive"))
      (node (ref "U1") (pin "15") (pinfunction "~{MCLR}_15") (pintype "bidirectional"))
    )
    (net (code "200") (name "~{SS6}") (class "Default")
      (node (ref "TFT") (pin "38") (pinfunction "/CS_38") (pintype "bidirectional"))
      (node (ref "U1") (pin "6") (pinfunction "PMA6_6") (pintype "bidirectional"))
      (node (ref "U1") (pin "68") (pinfunction "PMA15_68") (pintype "bidirectional"))
    )
  )
)
